# Power.net
KiCad netlist of a schematic drawn in Altium Designer
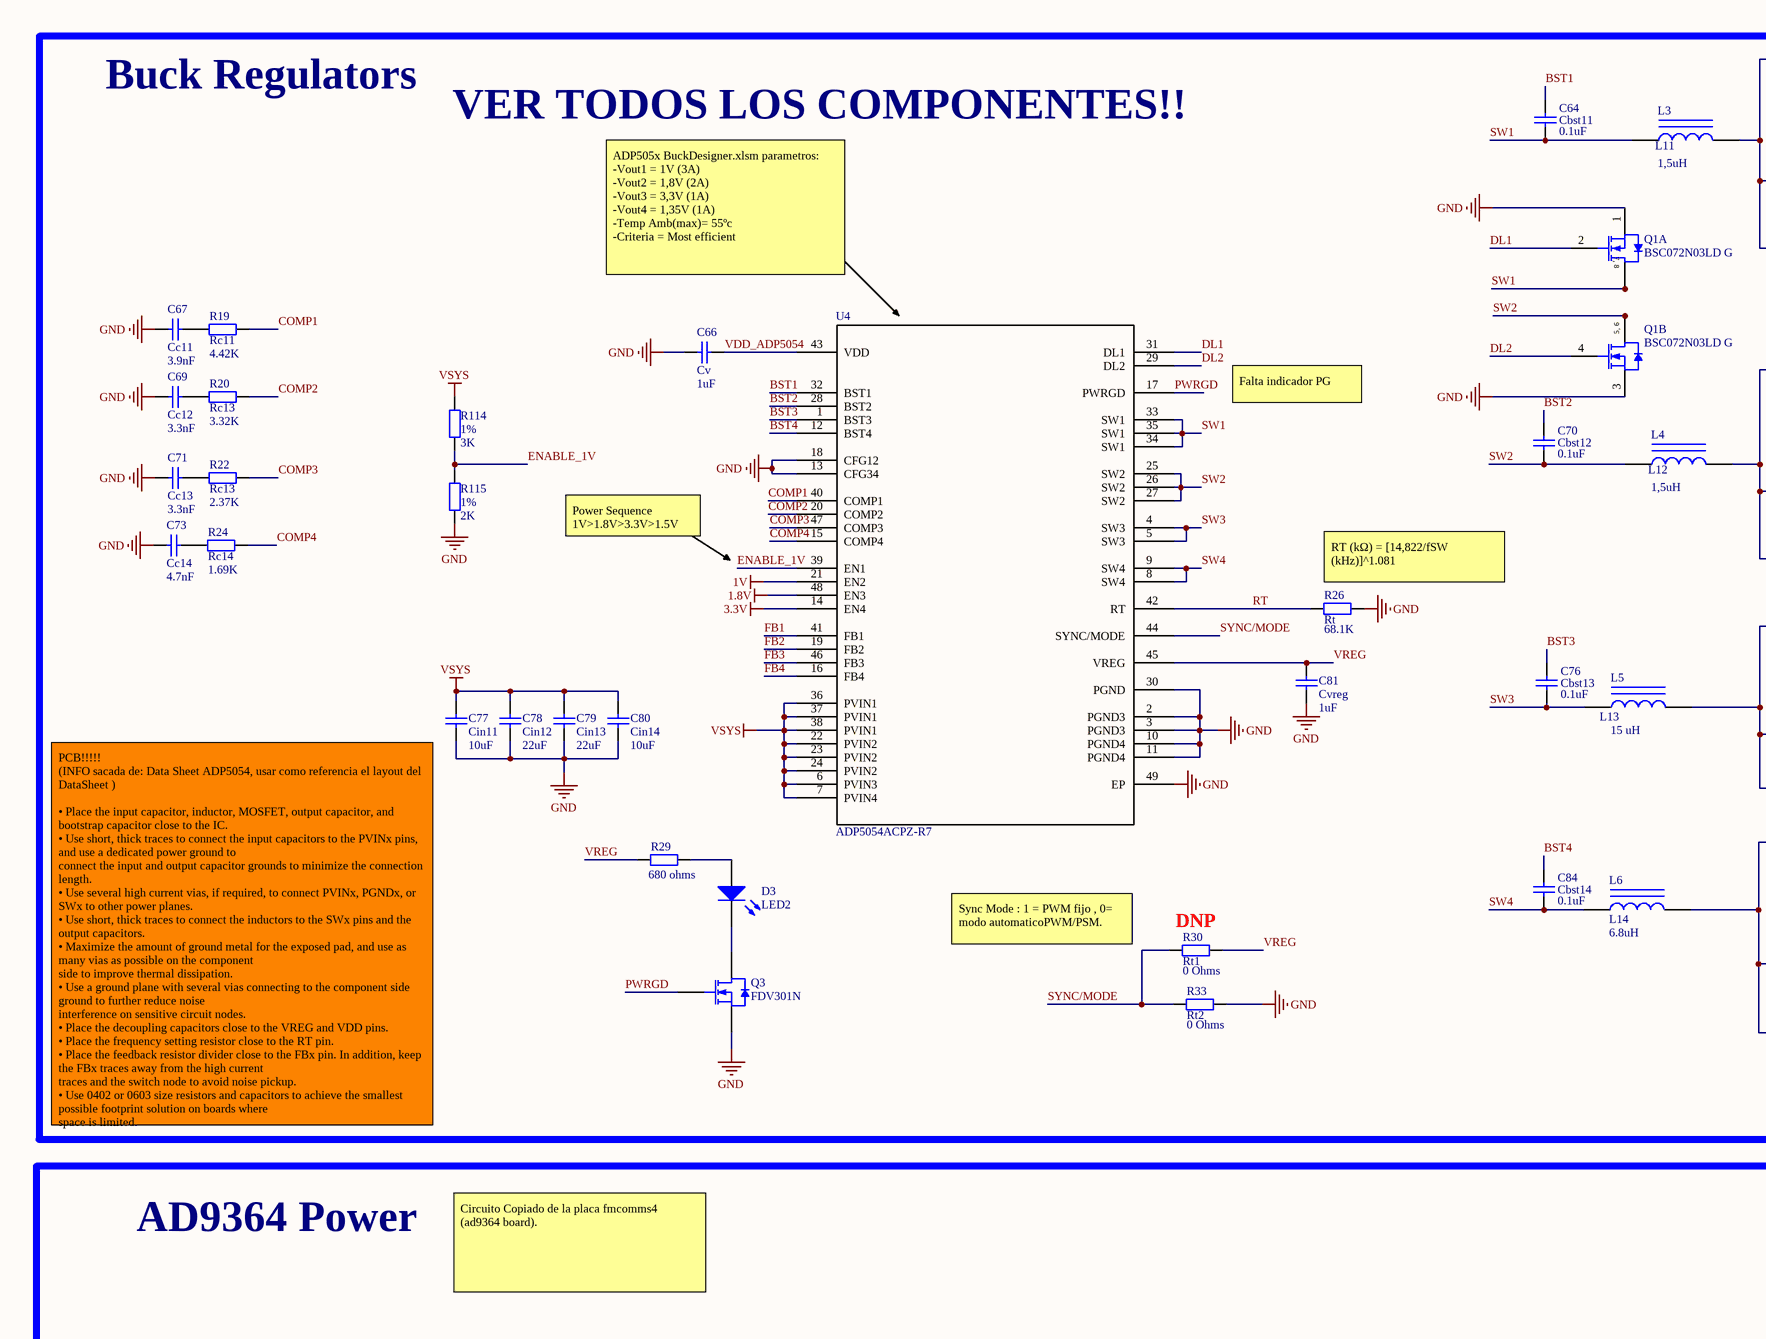
[diagram p0: Power.SchDoc, top left]
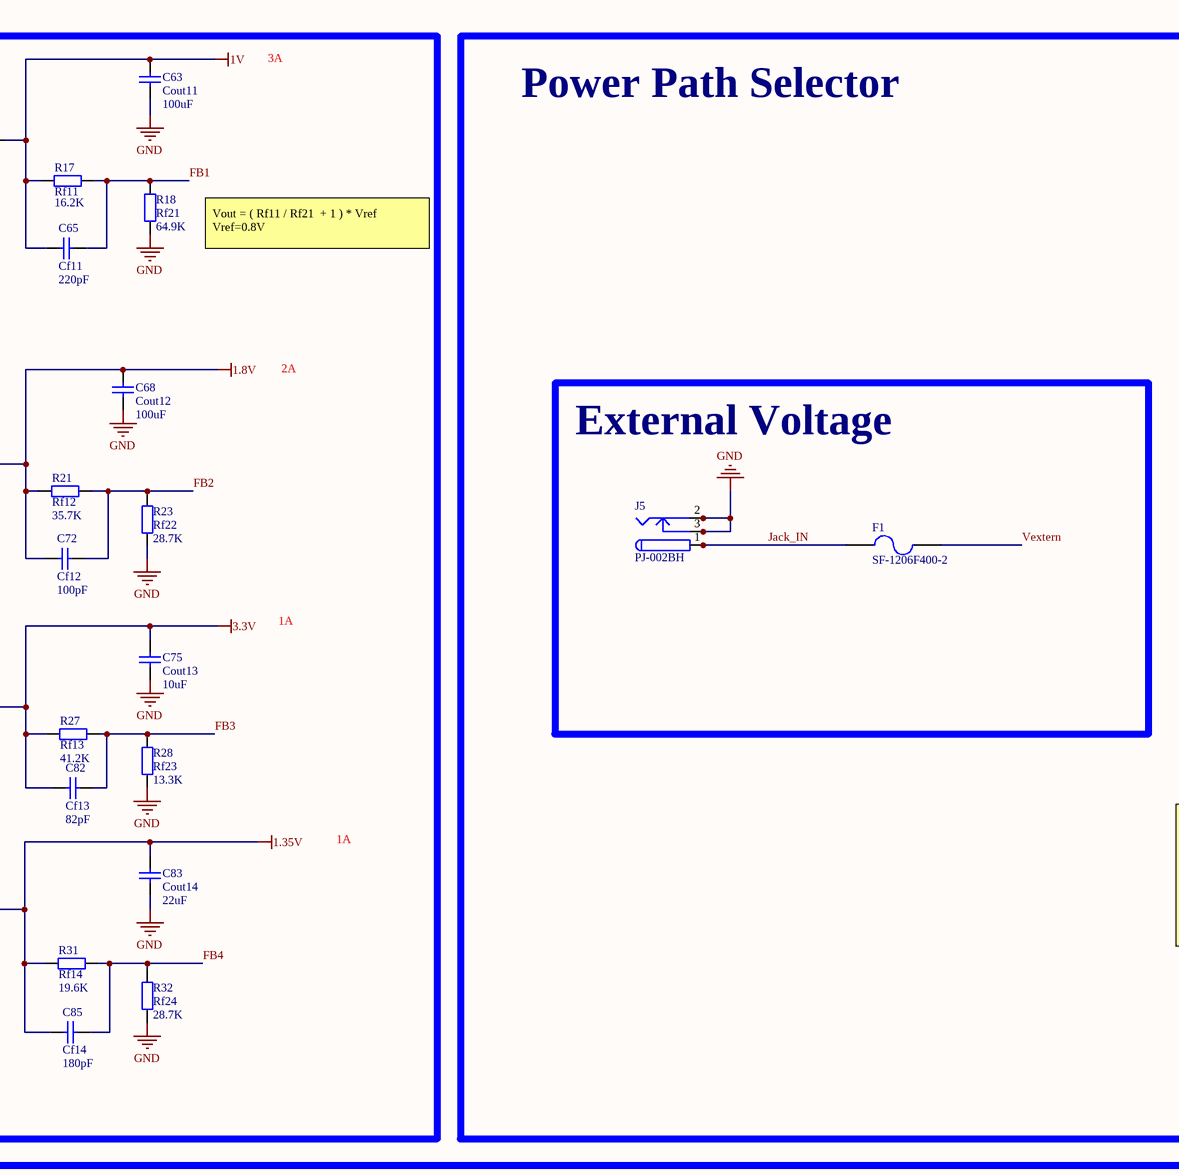
[diagram p1: Power.SchDoc, top middle]
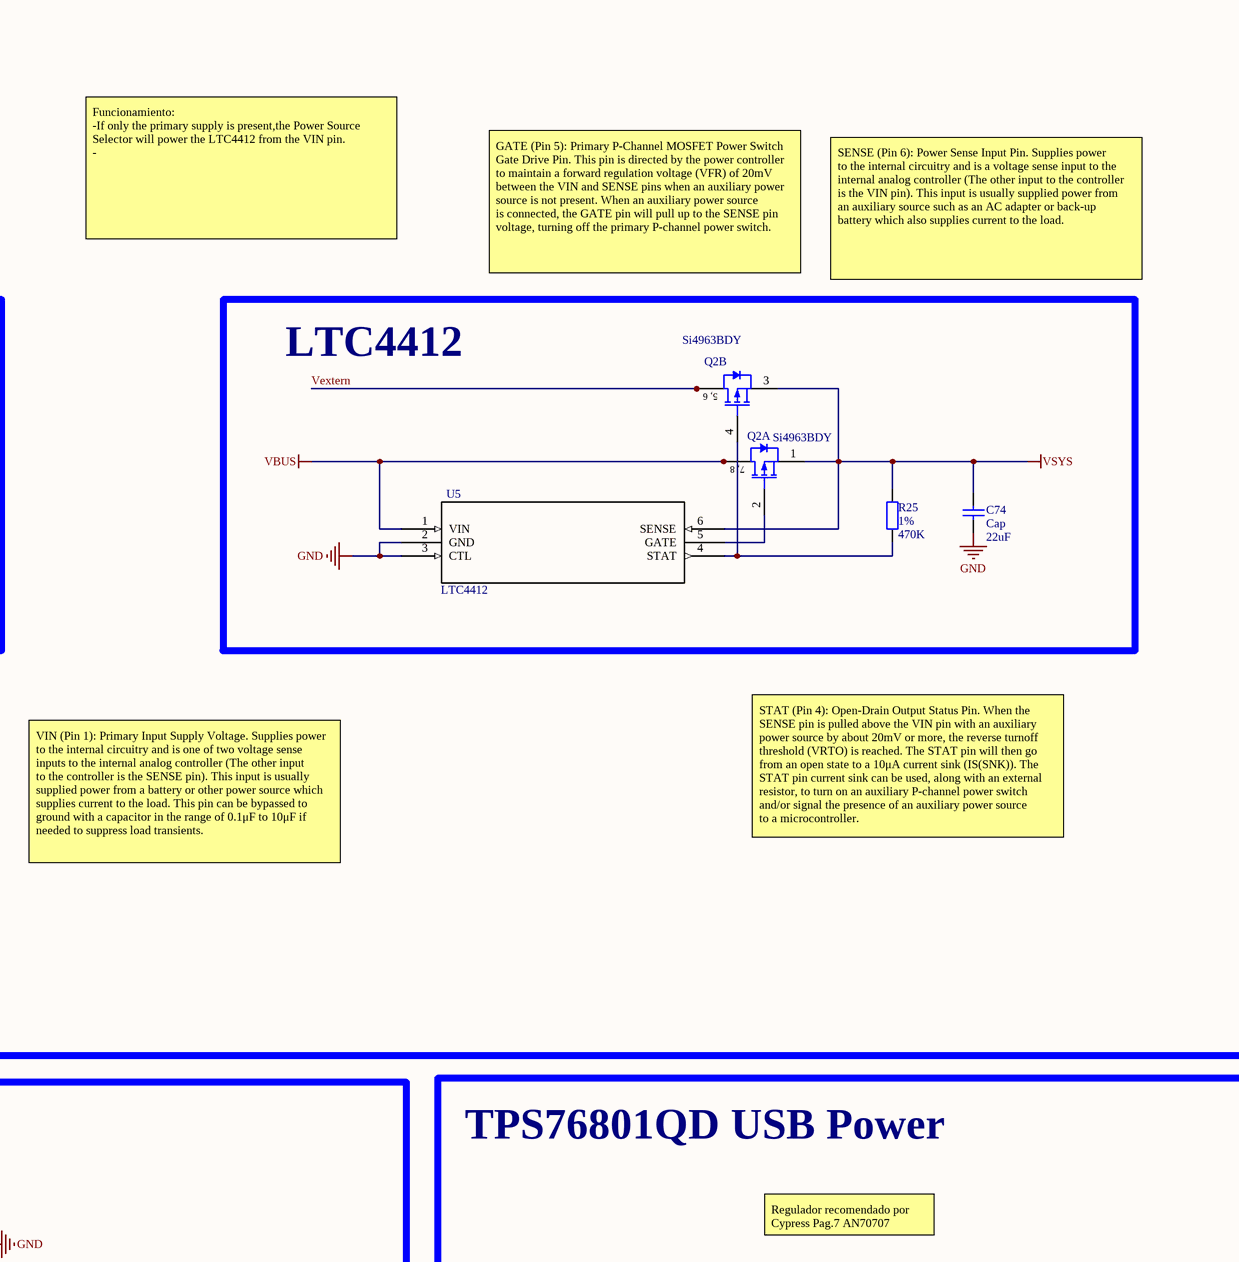
[diagram p2: Power.SchDoc, top right]
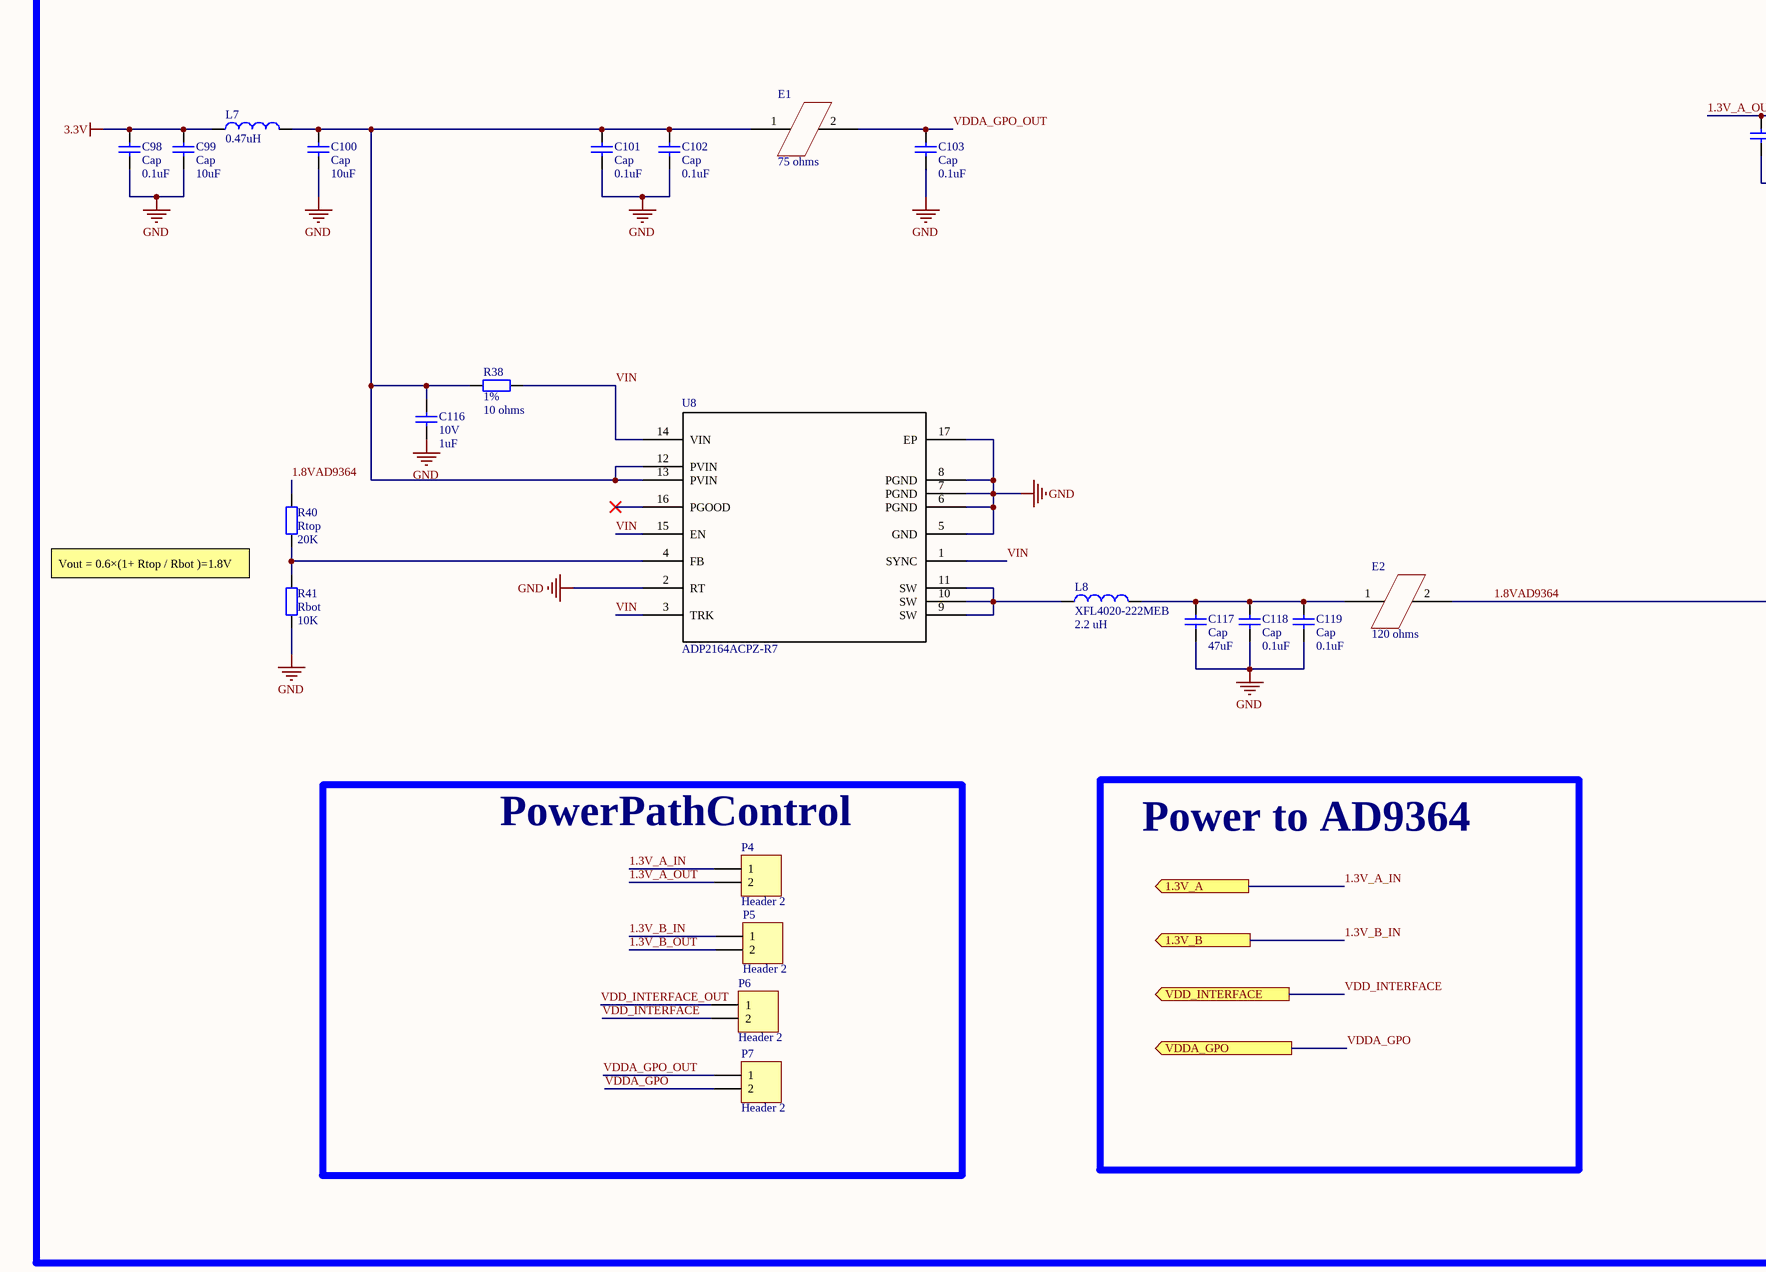
[diagram p3: Power.SchDoc, bottom left]
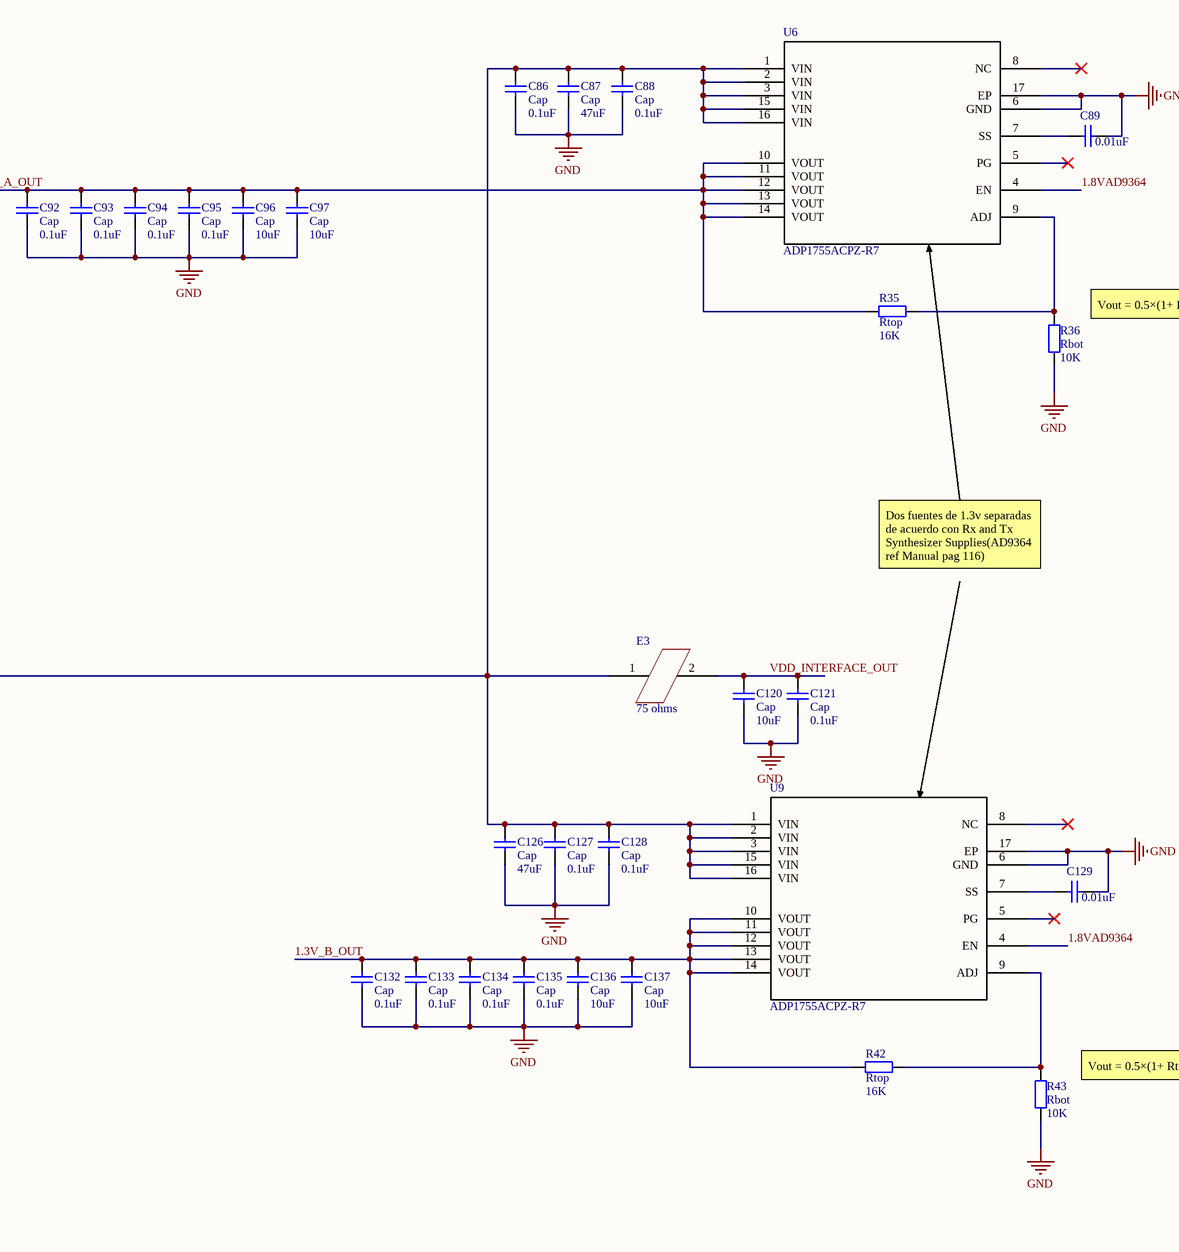
[diagram p4: Power.SchDoc, bottom middle]
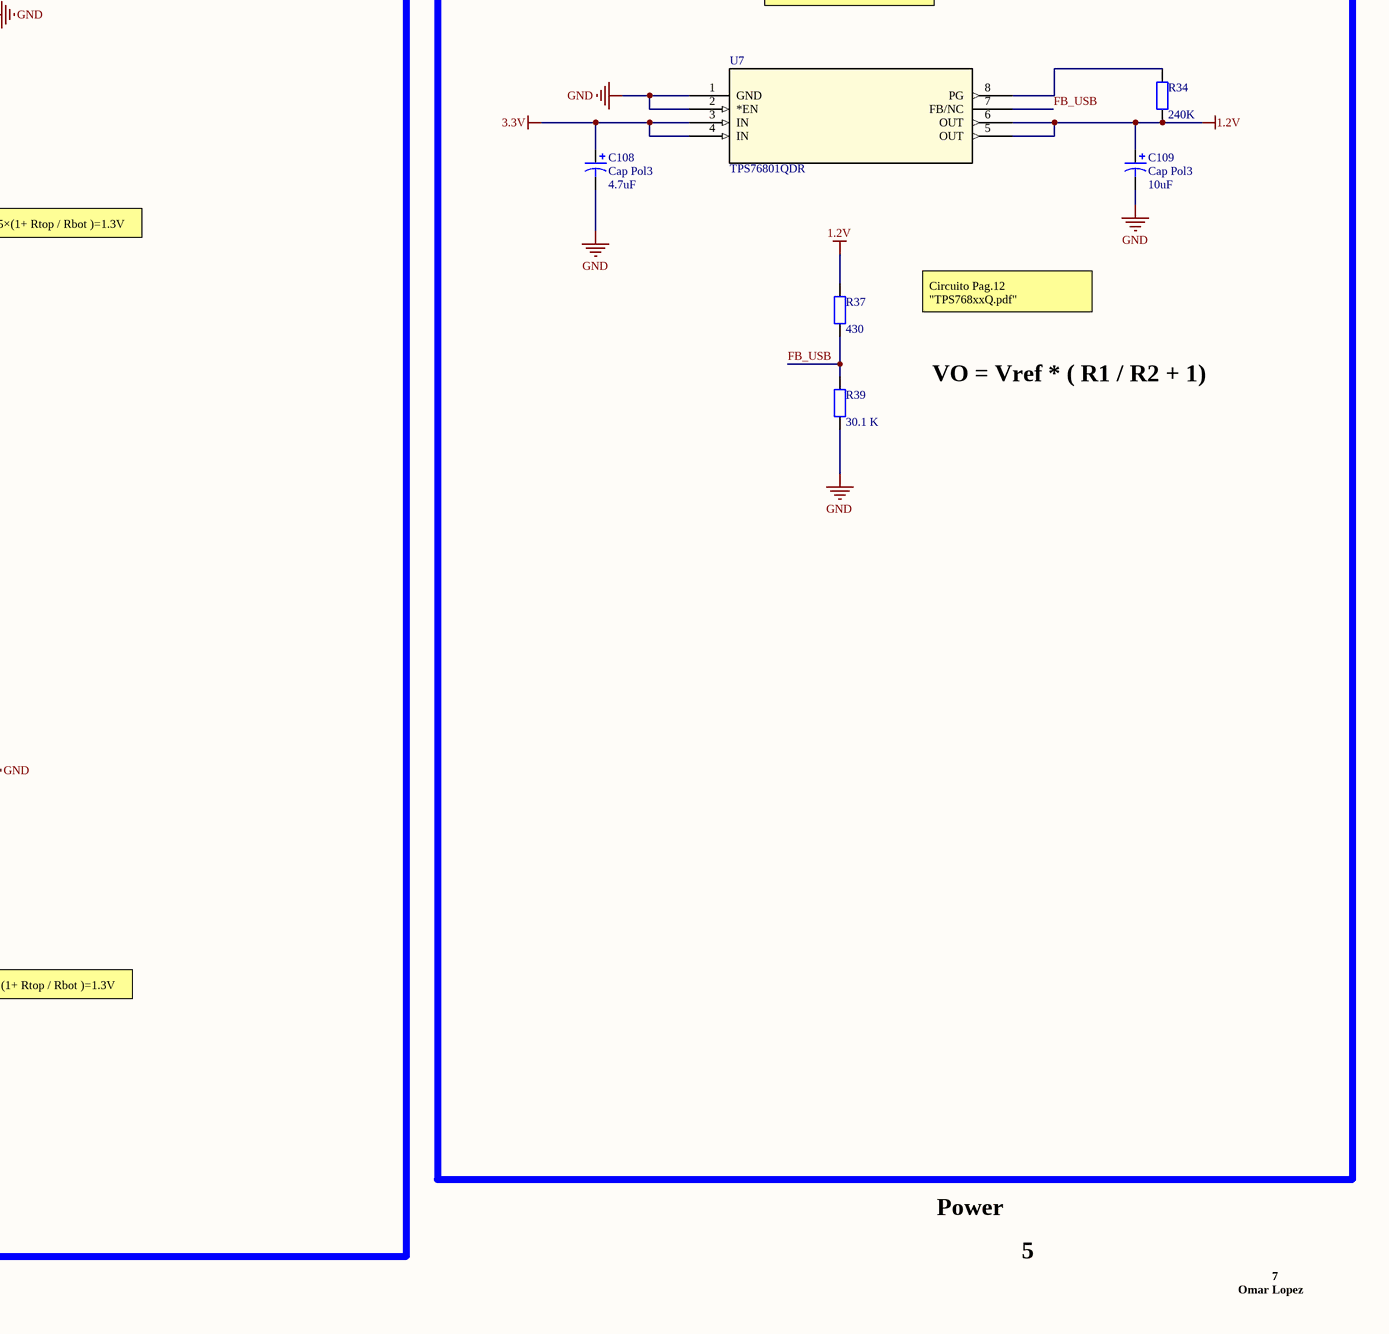
[diagram p5: Power.SchDoc, bottom right]

(export (version "E")
  (design (tool "Eeschema 10.0.6"))
  (components
    (comp (ref "C63")
      (value "Cout11")
      (footprint "MurataCapacitor:GRM1206MurataCap")
      (description "Capacitor")
      (fields
        (field (name "ALTIUM_VALUE") "100uF")
        (field (name "MANUFACTURER") "TDK")
        (field (name "TOLERANCE") "20%")
      )
      (libsource (lib "Miscellaneous Devices") (part "Cap"))
    )
    (comp (ref "C64")
      (value "Cbst11")
      (footprint "GRM0402MurataCap")
      (description "Capacitor")
      (fields
        (field (name "MANUFACTURER") "Murata")
        (field (name "PARTNUMBER") "GRM152D70G104ME15D")
        (field (name "ALTIUM_VALUE") "0.1uF")
      )
      (libsource (lib "Miscellaneous Devices") (part "Cap"))
    )
    (comp (ref "C65")
      (value "Cf11")
      (footprint "MurataCapacitor:GRM0402MurataCap")
      (description "Capacitor")
      (fields
        (field (name "ALTIUM_VALUE") "220pF")
        (field (name "MANUFACTURER") "Murata")
        (field (name "TOLERANCE") "5%")
      )
      (libsource (lib "Miscellaneous Devices") (part "Cap"))
    )
    (comp (ref "C66")
      (value "Cv")
      (footprint "MurataCapacitor:GRM0402MurataCap")
      (description "Capacitor")
      (fields
        (field (name "ALTIUM_VALUE") "1uF")
        (field (name "MANUFACTURER") "Murata")
        (field (name "TOLERANCE") "10%")
      )
      (libsource (lib "Miscellaneous Devices") (part "Cap"))
    )
    (comp (ref "C67")
      (value "Cc11")
      (footprint "MurataCapacitor:GRM0402MurataCap")
      (description "Capacitor")
      (fields
        (field (name "ALTIUM_VALUE") "3.9nF")
        (field (name "MANUFACTURER") "Murata")
        (field (name "TOLERANCE") "10%")
      )
      (libsource (lib "Miscellaneous Devices") (part "Cap"))
    )
    (comp (ref "C68")
      (value "Cout12")
      (footprint "MurataCapacitor:GRM1206MurataCap")
      (description "Capacitor")
      (fields
        (field (name "ALTIUM_VALUE") "100uF")
        (field (name "MANUFACTURER") "TDK")
        (field (name "TOLERANCE") "20%")
      )
      (libsource (lib "Miscellaneous Devices") (part "Cap"))
    )
    (comp (ref "C69")
      (value "Cc12")
      (footprint "MurataCapacitor:GRM0402MurataCap")
      (description "Capacitor")
      (fields
        (field (name "ALTIUM_VALUE") "3.3nF")
        (field (name "MANUFACTURER") "Murata")
        (field (name "TOLERANCE") "10%")
      )
      (libsource (lib "Miscellaneous Devices") (part "Cap"))
    )
    (comp (ref "C70")
      (value "Cbst12")
      (footprint "GRM0402MurataCap")
      (description "Capacitor")
      (fields
        (field (name "MANUFACTURER") "Murata")
        (field (name "PARTNUMBER") "GRM152D70G104ME15D")
        (field (name "ALTIUM_VALUE") "0.1uF")
      )
      (libsource (lib "Miscellaneous Devices") (part "Cap"))
    )
    (comp (ref "C71")
      (value "Cc13")
      (footprint "MurataCapacitor:GRM0402MurataCap")
      (description "Capacitor")
      (fields
        (field (name "ALTIUM_VALUE") "3.3nF")
        (field (name "MANUFACTURER") "Murata")
        (field (name "TOLERANCE") "10%")
      )
      (libsource (lib "Miscellaneous Devices") (part "Cap"))
    )
    (comp (ref "C72")
      (value "Cf12")
      (footprint "MurataCapacitor:GRM0402MurataCap")
      (description "Capacitor")
      (fields
        (field (name "ALTIUM_VALUE") "100pF")
        (field (name "MANUFACTURER") "Murata")
        (field (name "TOLERANCE") "2%")
      )
      (libsource (lib "Miscellaneous Devices") (part "Cap"))
    )
    (comp (ref "C73")
      (value "Cc14")
      (footprint "MurataCapacitor:GRM0402MurataCap")
      (description "Capacitor")
      (fields
        (field (name "ALTIUM_VALUE") "4.7nF")
        (field (name "MANUFACTURER") "Murata")
        (field (name "TOLERANCE") "10%")
      )
      (libsource (lib "Miscellaneous Devices") (part "Cap"))
    )
    (comp (ref "C74")
      (value "Cap")
      (footprint "MurataCapacitor:GRM1210MurataCap")
      (description "Capacitor")
      (fields
        (field (name "ALTIUM_VALUE") "22uF")
        (field (name "MANUFACTURER") "Taiyo Yuden")
        (field (name "TOLERANCE") "20%")
      )
      (libsource (lib "Miscellaneous Devices") (part "Cap"))
    )
    (comp (ref "C75")
      (value "Cout13")
      (footprint "MurataCapacitor:GRM1206MurataCap")
      (description "Capacitor")
      (fields
        (field (name "ALTIUM_VALUE") "10uF")
        (field (name "MANUFACTURER") "Taiyo Yuden")
        (field (name "TOLERANCE") "20%")
      )
      (libsource (lib "Miscellaneous Devices") (part "Cap"))
    )
    (comp (ref "C76")
      (value "Cbst13")
      (footprint "GRM0402MurataCap")
      (description "Capacitor")
      (fields
        (field (name "MANUFACTURER") "Murata")
        (field (name "PARTNUMBER") "GRM152D70G104ME15D")
        (field (name "ALTIUM_VALUE") "0.1uF")
      )
      (libsource (lib "Miscellaneous Devices") (part "Cap"))
    )
    (comp (ref "C77")
      (value "Cin11")
      (footprint "MurataCapacitor:GRM1210MurataCap")
      (description "Capacitor")
      (fields
        (field (name "ALTIUM_VALUE") "10uF")
        (field (name "MANUFACTURER") "Murata")
        (field (name "TOLERANCE") "10%")
      )
      (libsource (lib "Miscellaneous Devices") (part "Cap"))
    )
    (comp (ref "C78")
      (value "Cin12")
      (footprint "MurataCapacitor:GRM1210MurataCap")
      (description "Capacitor")
      (fields
        (field (name "ALTIUM_VALUE") "22uF")
        (field (name "MANUFACTURER") "Taiyo Yuden")
        (field (name "TOLERANCE") "20%")
      )
      (libsource (lib "Miscellaneous Devices") (part "Cap"))
    )
    (comp (ref "C79")
      (value "Cin13")
      (footprint "MurataCapacitor:GRM1210MurataCap")
      (description "Capacitor")
      (fields
        (field (name "ALTIUM_VALUE") "22uF")
        (field (name "MANUFACTURER") "Taiyo Yuden")
        (field (name "TOLERANCE") "20%")
      )
      (libsource (lib "Miscellaneous Devices") (part "Cap"))
    )
    (comp (ref "C80")
      (value "Cin14")
      (footprint "MurataCapacitor:GRM1210MurataCap")
      (description "Capacitor")
      (fields
        (field (name "ALTIUM_VALUE") "10uF")
        (field (name "MANUFACTURER") "Murata")
        (field (name "TOLERANCE") "10%")
      )
      (libsource (lib "Miscellaneous Devices") (part "Cap"))
    )
    (comp (ref "C81")
      (value "Cvreg")
      (footprint "MurataCapacitor:GRM0402MurataCap")
      (description "Capacitor")
      (fields
        (field (name "ALTIUM_VALUE") "1uF")
        (field (name "MANUFACTURER") "Murata")
        (field (name "TOLERANCE") "10%")
      )
      (libsource (lib "Miscellaneous Devices") (part "Cap"))
    )
    (comp (ref "C82")
      (value "Cf13")
      (footprint "MurataCapacitor:GRM0402MurataCap")
      (description "Capacitor")
      (fields
        (field (name "ALTIUM_VALUE") "82pF")
        (field (name "MANUFACTURER") "Murata")
        (field (name "TOLERANCE") "10%")
      )
      (libsource (lib "Miscellaneous Devices") (part "Cap"))
    )
    (comp (ref "C83")
      (value "Cout14")
      (footprint "MurataCapacitor:GRM1206MurataCap")
      (description "Capacitor")
      (fields
        (field (name "ALTIUM_VALUE") "22uF")
        (field (name "MANUFACTURER") "Taiyo Yuden")
        (field (name "TOLERANCE") "20%")
      )
      (libsource (lib "Miscellaneous Devices") (part "Cap"))
    )
    (comp (ref "C84")
      (value "Cbst14")
      (footprint "GRM0402MurataCap")
      (description "Capacitor")
      (fields
        (field (name "MANUFACTURER") "Murata")
        (field (name "PARTNUMBER") "GRM152D70G104ME15D")
        (field (name "ALTIUM_VALUE") "0.1uF")
      )
      (libsource (lib "Miscellaneous Devices") (part "Cap"))
    )
    (comp (ref "C85")
      (value "Cf14")
      (footprint "MurataCapacitor:GRM0402MurataCap")
      (description "Capacitor")
      (fields
        (field (name "ALTIUM_VALUE") "180pF")
        (field (name "MANUFACTURER") "Murata")
        (field (name "TOLERANCE") "5%")
      )
      (libsource (lib "Miscellaneous Devices") (part "Cap"))
    )
    (comp (ref "C86")
      (value "Cap")
      (footprint "MurataCapacitor:GRM0402MurataCap")
      (description "Capacitor")
      (fields
        (field (name "ALTIUM_VALUE") "0.1uF")
        (field (name "MANUFACTURER") "Murata")
        (field (name "TOLERANCE") "10%")
      )
      (libsource (lib "Miscellaneous Devices") (part "Cap"))
    )
    (comp (ref "C87")
      (value "Cap")
      (footprint "MurataCapacitor:GRM0805MurataCap")
      (description "Capacitor")
      (fields
        (field (name "ALTIUM_VALUE") "47uF")
        (field (name "MANUFACTURER") "Murata")
        (field (name "TOLERANCE") "20%")
      )
      (libsource (lib "Miscellaneous Devices") (part "Cap"))
    )
    (comp (ref "C88")
      (value "Cap")
      (footprint "MurataCapacitor:GRM0402MurataCap")
      (description "Capacitor")
      (fields
        (field (name "ALTIUM_VALUE") "0.1uF")
        (field (name "MANUFACTURER") "Murata")
        (field (name "TOLERANCE") "10%")
      )
      (libsource (lib "Miscellaneous Devices") (part "Cap"))
    )
    (comp (ref "C89")
      (value "0.01uF")
      (footprint "MurataCapacitor:GRM0402MurataCap")
      (description "Capacitor")
      (fields (field (name "MANUFACTURER") "Murata") (field (name "TOLERANCE") "10%"))
      (libsource (lib "Miscellaneous Devices") (part "Cap"))
    )
    (comp (ref "C92")
      (value "Cap")
      (footprint "MurataCapacitor:GRM0402MurataCap")
      (description "Capacitor")
      (fields
        (field (name "ALTIUM_VALUE") "0.1uF")
        (field (name "MANUFACTURER") "Murata")
        (field (name "TOLERANCE") "10%")
      )
      (libsource (lib "Miscellaneous Devices") (part "Cap"))
    )
    (comp (ref "C93")
      (value "Cap")
      (footprint "MurataCapacitor:GRM0402MurataCap")
      (description "Capacitor")
      (fields
        (field (name "ALTIUM_VALUE") "0.1uF")
        (field (name "MANUFACTURER") "Murata")
        (field (name "TOLERANCE") "10%")
      )
      (libsource (lib "Miscellaneous Devices") (part "Cap"))
    )
    (comp (ref "C94")
      (value "Cap")
      (footprint "MurataCapacitor:GRM0402MurataCap")
      (description "Capacitor")
      (fields
        (field (name "ALTIUM_VALUE") "0.1uF")
        (field (name "MANUFACTURER") "Murata")
        (field (name "TOLERANCE") "10%")
      )
      (libsource (lib "Miscellaneous Devices") (part "Cap"))
    )
    (comp (ref "C95")
      (value "Cap")
      (footprint "MurataCapacitor:GRM0402MurataCap")
      (description "Capacitor")
      (fields
        (field (name "ALTIUM_VALUE") "0.1uF")
        (field (name "MANUFACTURER") "Murata")
        (field (name "TOLERANCE") "10%")
      )
      (libsource (lib "Miscellaneous Devices") (part "Cap"))
    )
    (comp (ref "C96")
      (value "Cap")
      (footprint "MurataCapacitor:GRM0603MurataCap")
      (description "Capacitor")
      (fields
        (field (name "ALTIUM_VALUE") "10uF")
        (field (name "MANUFACTURER") "Murata")
        (field (name "TOLERANCE") "20%")
      )
      (libsource (lib "Miscellaneous Devices") (part "Cap"))
    )
    (comp (ref "C97")
      (value "Cap")
      (footprint "MurataCapacitor:GRM0603MurataCap")
      (description "Capacitor")
      (fields
        (field (name "ALTIUM_VALUE") "10uF")
        (field (name "MANUFACTURER") "Murata")
        (field (name "TOLERANCE") "20%")
      )
      (libsource (lib "Miscellaneous Devices") (part "Cap"))
    )
    (comp (ref "C98")
      (value "Cap")
      (footprint "MurataCapacitor:GRM0402MurataCap")
      (description "Capacitor")
      (fields
        (field (name "ALTIUM_VALUE") "0.1uF")
        (field (name "MANUFACTURER") "Murata")
        (field (name "TOLERANCE") "10%")
      )
      (libsource (lib "Miscellaneous Devices") (part "Cap"))
    )
    (comp (ref "C99")
      (value "Cap")
      (footprint "MurataCapacitor:GRM0603MurataCap")
      (description "Capacitor")
      (fields
        (field (name "ALTIUM_VALUE") "10uF")
        (field (name "MANUFACTURER") "Murata")
        (field (name "TOLERANCE") "20%")
      )
      (libsource (lib "Miscellaneous Devices") (part "Cap"))
    )
    (comp (ref "C100")
      (value "Cap")
      (footprint "MurataCapacitor:GRM0603MurataCap")
      (description "Capacitor")
      (fields
        (field (name "ALTIUM_VALUE") "10uF")
        (field (name "MANUFACTURER") "Murata")
        (field (name "TOLERANCE") "20%")
      )
      (libsource (lib "Miscellaneous Devices") (part "Cap"))
    )
    (comp (ref "C101")
      (value "Cap")
      (footprint "MurataCapacitor:GRM0402MurataCap")
      (description "Capacitor")
      (fields
        (field (name "ALTIUM_VALUE") "0.1uF")
        (field (name "MANUFACTURER") "Murata")
        (field (name "TOLERANCE") "10%")
      )
      (libsource (lib "Miscellaneous Devices") (part "Cap"))
    )
    (comp (ref "C102")
      (value "Cap")
      (footprint "MurataCapacitor:GRM0402MurataCap")
      (description "Capacitor")
      (fields
        (field (name "ALTIUM_VALUE") "0.1uF")
        (field (name "MANUFACTURER") "Murata")
        (field (name "TOLERANCE") "10%")
      )
      (libsource (lib "Miscellaneous Devices") (part "Cap"))
    )
    (comp (ref "C103")
      (value "Cap")
      (footprint "MurataCapacitor:GRM0402MurataCap")
      (description "Capacitor")
      (fields
        (field (name "ALTIUM_VALUE") "0.1uF")
        (field (name "MANUFACTURER") "Murata")
        (field (name "TOLERANCE") "10%")
      )
      (libsource (lib "Miscellaneous Devices") (part "Cap"))
    )
    (comp (ref "C108")
      (value "Cap Pol3")
      (footprint "CapTal:CapTalCaseM")
      (description "Polarized Capacitor (Surface Mount)")
      (fields
        (field (name "ALTIUM_VALUE") "4.7uF")
        (field (name "TOLERANCE") "20%")
        (field (name "PARTNUMBER") "298D475X0016M2T")
      )
      (libsource (lib "Miscellaneous Devices") (part "Cap Pol3"))
    )
    (comp (ref "C109")
      (value "Cap Pol3")
      (footprint "TAJ_Cap:TAJ_DorE2917")
      (description "Polarized Capacitor (Surface Mount)")
      (fields
        (field (name "ALTIUM_VALUE") "10uF")
        (field (name "TOLERANCE") "30%")
        (field (name "PARTNUMBER") "TAJD106K035RNJ")
      )
      (libsource (lib "Miscellaneous Devices") (part "Cap Pol3"))
    )
    (comp (ref "C116")
      (value "10V")
      (footprint "MurataCapacitor:GRM0402MurataCap")
      (description "Capacitor")
      (fields
        (field (name "ALTIUM_VALUE") "1uF")
        (field (name "MANUFACTURER") "Murata")
        (field (name "TOLERANCE") "10%")
      )
      (libsource (lib "Miscellaneous Devices") (part "Cap"))
    )
    (comp (ref "C117")
      (value "Cap")
      (footprint "MurataCapacitor:GRM0805MurataCap")
      (description "Capacitor")
      (fields
        (field (name "ALTIUM_VALUE") "47uF")
        (field (name "MANUFACTURER") "Murata")
        (field (name "TOLERANCE") "20%")
      )
      (libsource (lib "Miscellaneous Devices") (part "Cap"))
    )
    (comp (ref "C118")
      (value "Cap")
      (footprint "MurataCapacitor:GRM0402MurataCap")
      (description "Capacitor")
      (fields
        (field (name "ALTIUM_VALUE") "0.1uF")
        (field (name "MANUFACTURER") "Murata")
        (field (name "TOLERANCE") "10%")
      )
      (libsource (lib "Miscellaneous Devices") (part "Cap"))
    )
    (comp (ref "C119")
      (value "Cap")
      (footprint "MurataCapacitor:GRM0402MurataCap")
      (description "Capacitor")
      (fields
        (field (name "ALTIUM_VALUE") "0.1uF")
        (field (name "MANUFACTURER") "Murata")
        (field (name "TOLERANCE") "10%")
      )
      (libsource (lib "Miscellaneous Devices") (part "Cap"))
    )
    (comp (ref "C120")
      (value "Cap")
      (footprint "MurataCapacitor:GRM0603MurataCap")
      (description "Capacitor")
      (fields
        (field (name "ALTIUM_VALUE") "10uF")
        (field (name "MANUFACTURER") "Murata")
        (field (name "TOLERANCE") "20%")
      )
      (libsource (lib "Miscellaneous Devices") (part "Cap"))
    )
    (comp (ref "C121")
      (value "Cap")
      (footprint "MurataCapacitor:GRM0402MurataCap")
      (description "Capacitor")
      (fields
        (field (name "ALTIUM_VALUE") "0.1uF")
        (field (name "MANUFACTURER") "Murata")
        (field (name "TOLERANCE") "10%")
      )
      (libsource (lib "Miscellaneous Devices") (part "Cap"))
    )
    (comp (ref "C126")
      (value "Cap")
      (footprint "MurataCapacitor:GRM0805MurataCap")
      (description "Capacitor")
      (fields
        (field (name "ALTIUM_VALUE") "47uF")
        (field (name "MANUFACTURER") "Murata")
        (field (name "TOLERANCE") "20%")
      )
      (libsource (lib "Miscellaneous Devices") (part "Cap"))
    )
    (comp (ref "C127")
      (value "Cap")
      (footprint "MurataCapacitor:GRM0402MurataCap")
      (description "Capacitor")
      (fields
        (field (name "ALTIUM_VALUE") "0.1uF")
        (field (name "MANUFACTURER") "Murata")
        (field (name "TOLERANCE") "10%")
      )
      (libsource (lib "Miscellaneous Devices") (part "Cap"))
    )
    (comp (ref "C128")
      (value "Cap")
      (footprint "MurataCapacitor:GRM0402MurataCap")
      (description "Capacitor")
      (fields
        (field (name "ALTIUM_VALUE") "0.1uF")
        (field (name "MANUFACTURER") "Murata")
        (field (name "TOLERANCE") "10%")
      )
      (libsource (lib "Miscellaneous Devices") (part "Cap"))
    )
    (comp (ref "C129")
      (value "0.01uF")
      (footprint "MurataCapacitor:GRM0402MurataCap")
      (description "Capacitor")
      (fields (field (name "MANUFACTURER") "Murata") (field (name "TOLERANCE") "10%"))
      (libsource (lib "Miscellaneous Devices") (part "Cap"))
    )
    (comp (ref "C132")
      (value "Cap")
      (footprint "MurataCapacitor:GRM0402MurataCap")
      (description "Capacitor")
      (fields
        (field (name "ALTIUM_VALUE") "0.1uF")
        (field (name "MANUFACTURER") "Murata")
        (field (name "TOLERANCE") "10%")
      )
      (libsource (lib "Miscellaneous Devices") (part "Cap"))
    )
    (comp (ref "C133")
      (value "Cap")
      (footprint "MurataCapacitor:GRM0402MurataCap")
      (description "Capacitor")
      (fields
        (field (name "ALTIUM_VALUE") "0.1uF")
        (field (name "MANUFACTURER") "Murata")
        (field (name "TOLERANCE") "10%")
      )
      (libsource (lib "Miscellaneous Devices") (part "Cap"))
    )
    (comp (ref "C134")
      (value "Cap")
      (footprint "MurataCapacitor:GRM0402MurataCap")
      (description "Capacitor")
      (fields
        (field (name "ALTIUM_VALUE") "0.1uF")
        (field (name "MANUFACTURER") "Murata")
        (field (name "TOLERANCE") "10%")
      )
      (libsource (lib "Miscellaneous Devices") (part "Cap"))
    )
    (comp (ref "C135")
      (value "Cap")
      (footprint "MurataCapacitor:GRM0402MurataCap")
      (description "Capacitor")
      (fields
        (field (name "ALTIUM_VALUE") "0.1uF")
        (field (name "MANUFACTURER") "Murata")
        (field (name "TOLERANCE") "10%")
      )
      (libsource (lib "Miscellaneous Devices") (part "Cap"))
    )
    (comp (ref "C136")
      (value "Cap")
      (footprint "MurataCapacitor:GRM0603MurataCap")
      (description "Capacitor")
      (fields
        (field (name "ALTIUM_VALUE") "10uF")
        (field (name "MANUFACTURER") "Murata")
        (field (name "TOLERANCE") "20%")
      )
      (libsource (lib "Miscellaneous Devices") (part "Cap"))
    )
    (comp (ref "C137")
      (value "Cap")
      (footprint "MurataCapacitor:GRM0603MurataCap")
      (description "Capacitor")
      (fields
        (field (name "ALTIUM_VALUE") "10uF")
        (field (name "MANUFACTURER") "Murata")
        (field (name "TOLERANCE") "20%")
      )
      (libsource (lib "Miscellaneous Devices") (part "Cap"))
    )
    (comp (ref "D3")
      (value "LED2")
      (footprint "LiteOnLed:LTSTC191")
      (description "Typical RED, GREEN, YELLOW, AMBER GaAs LED")
      (fields (field (name "MANUFACTURER") "Panasonic") (field (name "PARTNUMBER") "LTST-C193TGKT-5A"))
      (libsource (lib "Miscellaneous Devices") (part "LED2"))
    )
    (comp (ref "E1")
      (value "75 ohms")
      (footprint "BLM15BA750SN1D:BLM15BA750SN1D")
      (description "Ferrite bead")
      (fields (field (name "MANUFACTURER") "Murata") (field (name "PARTNUMBER") "BLM15BA750SN1D"))
      (libsource (lib "FerriteBead") (part "Ferrite Bead"))
    )
    (comp (ref "E2")
      (value "120 ohms")
      (footprint "BLM15BA750SN1D:BLM15BA750SN1D")
      (description "Ferrite bead")
      (fields (field (name "MANUFACTURER") "Murata") (field (name "PARTNUMBER") "BLM15EG121SN1D"))
      (libsource (lib "FerriteBead") (part "Ferrite Bead"))
    )
    (comp (ref "E3")
      (value "75 ohms")
      (footprint "BLM15BA750SN1D:BLM15BA750SN1D")
      (description "Ferrite bead")
      (fields (field (name "MANUFACTURER") "Murata") (field (name "PARTNUMBER") "BLM15BA750SN1D"))
      (libsource (lib "FerriteBead") (part "Ferrite Bead"))
    )
    (comp (ref "F1")
      (value "SF-1206F400-2")
      (footprint "FUSE:SF-1206F400-2")
      (description "Fuse")
      (fields (field (name "MANUFACTURER") "Bourns"))
      (libsource (lib "Miscellaneous Devices") (part "Fuse 2"))
    )
    (comp (ref "J5")
      (value "PJ-002BH")
      (footprint "DCPowerJack:PJ-002BH")
      (description "Low Voltage Power Supply Connector")
      (fields (field (name "MANUFACTURER") "CUI"))
      (libsource (lib "Miscellaneous Connectors") (part "PWR2.5"))
    )
    (comp (ref "L3")
      (value "L11")
      (footprint "CoilcraftPCB:XAL4040-152")
      (description "Magnetic-Core Inductor")
      (fields
        (field (name "ALTIUM_VALUE") "1,5uH")
        (field (name "MANUFACTURER") "Coilcraft")
        (field (name "TOLERANCE") "20%")
      )
      (libsource (lib "Miscellaneous Devices") (part "Inductor Iron"))
    )
    (comp (ref "L4")
      (value "L12")
      (footprint "CoilcraftPCB:XAL4040-152")
      (description "Magnetic-Core Inductor")
      (fields
        (field (name "ALTIUM_VALUE") "1,5uH")
        (field (name "MANUFACTURER") "Coilcraft")
        (field (name "TOLERANCE") "20%")
      )
      (libsource (lib "Miscellaneous Devices") (part "Inductor Iron"))
    )
    (comp (ref "L5")
      (value "L13")
      (footprint "CoilcraftPCB:XAL5050-153")
      (description "Magnetic-Core Inductor")
      (fields
        (field (name "ALTIUM_VALUE") "15 uH")
        (field (name "MANUFACTURER") "Coilcraft")
        (field (name "TOLERANCE") "20%")
      )
      (libsource (lib "Miscellaneous Devices") (part "Inductor Iron"))
    )
    (comp (ref "L6")
      (value "L14")
      (footprint "CoilcraftPCB:XAL8080-682")
      (description "Magnetic-Core Inductor")
      (fields
        (field (name "ALTIUM_VALUE") "6.8uH")
        (field (name "MANUFACTURER") "Coilcraft")
        (field (name "TOLERANCE") "20%")
      )
      (libsource (lib "Miscellaneous Devices") (part "Inductor Iron"))
    )
    (comp (ref "L7")
      (value "0.47uH")
      (footprint "LQH32PNR47NN0L:LQH32PNR47NN0L")
      (description "Inductor")
      (fields (field (name "MANUFACTURER") "Murata") (field (name "PARTNUMBER") "LQH32PNR47NN0L"))
      (libsource (lib "Miscellaneous Devices") (part "Inductor"))
    )
    (comp (ref "L8")
      (value "XFL4020-222MEB")
      (footprint "CoilcraftPCB:XFL4020 SERIES")
      (description "Inductor")
      (fields
        (field (name "ALTIUM_VALUE") "2.2 uH")
        (field (name "MANUFACTURER") "Coilcraft")
        (field (name "TOLERANCE") "20%")
      )
      (libsource (lib "Miscellaneous Devices") (part "Inductor"))
    )
    (comp (ref "P4")
      (value "Header 2")
      (footprint "Header2x1")
      (description "Header, 2-Pin")
      (fields (field (name "MANUFACTURER") "TE Connectivity") (field (name "PARTNUMBER") "826629"))
      (libsource (lib "Miscellaneous Connectors") (part "Header 2"))
    )
    (comp (ref "P5")
      (value "Header 2")
      (footprint "Header2x1")
      (description "Header, 2-Pin")
      (fields (field (name "MANUFACTURER") "TE Connectivity") (field (name "PARTNUMBER") "826629"))
      (libsource (lib "Miscellaneous Connectors") (part "Header 2"))
    )
    (comp (ref "P6")
      (value "Header 2")
      (footprint "Header2x1")
      (description "Header, 2-Pin")
      (fields (field (name "MANUFACTURER") "TE Connectivity") (field (name "PARTNUMBER") "826629"))
      (libsource (lib "Miscellaneous Connectors") (part "Header 2"))
    )
    (comp (ref "P7")
      (value "Header 2")
      (footprint "Header2x1")
      (description "Header, 2-Pin")
      (fields (field (name "MANUFACTURER") "TE Connectivity") (field (name "PARTNUMBER") "826629"))
      (libsource (lib "Miscellaneous Connectors") (part "Header 2"))
    )
    (comp (ref "Q1")
      (value "BSC072N03LD G")
      (footprint "INF-PG-TDSON-8-4_V")
      (fields (field (name "MANUFACTURER") "Infineon"))
      (libsource (lib "Infineon_Power_MOSFET") (part "BSC072N03LD G"))
    )
    (comp (ref "Q2")
      (value "Si4963BDY")
      (footprint "SO-8_N")
      (description "Dual P-Channel 30V (D-S)  MOSFET")
      (libsource (lib "Vishay Siliconix Discrete MOSFET") (part "SI4925DY"))
    )
    (comp (ref "Q3")
      (value "FDV301N")
      (footprint "SOT-23B")
      (description "N-Channel 60V (D-S), 175'C  MOSFET")
      (fields (field (name "MANUFACTURER") "On Semiconductor"))
      (libsource (lib "Vishay Siliconix Discrete MOSFET") (part "SUP70N06-14"))
    )
    (comp (ref "R17")
      (value "Rf11")
      (footprint "Res0402ERJ:RC0402N")
      (description "Resistor")
      (fields
        (field (name "ALTIUM_VALUE") "16.2K")
        (field (name "MANUFACTURER") "Panasonic")
        (field (name "TOLERANCE") "1%")
      )
      (libsource (lib "") (part "Res2_3"))
    )
    (comp (ref "R18")
      (value "Rf21")
      (footprint "Res0402ERJ:RC0402N")
      (description "Resistor")
      (fields
        (field (name "ALTIUM_VALUE") "64.9K")
        (field (name "MANUFACTURER") "Panasonic")
        (field (name "TOLERANCE") "1%")
      )
      (libsource (lib "") (part "Res2_2"))
    )
    (comp (ref "R19")
      (value "Rc11")
      (footprint "Res0402ERJ:RC0402N")
      (description "Resistor")
      (fields
        (field (name "ALTIUM_VALUE") "4.42K")
        (field (name "MANUFACTURER") "Panasonic")
        (field (name "TOLERANCE") "1%")
      )
      (libsource (lib "Miscellaneous Devices") (part "Res2"))
    )
    (comp (ref "R20")
      (value "Rc13")
      (footprint "Res0402ERJ:RC0402N")
      (description "Resistor")
      (fields
        (field (name "ALTIUM_VALUE") "3.32K")
        (field (name "MANUFACTURER") "Panasonic")
        (field (name "TOLERANCE") "1%")
      )
      (libsource (lib "Miscellaneous Devices") (part "Res2"))
    )
    (comp (ref "R21")
      (value "Rf12")
      (footprint "Res0402ERJ:RC0402N")
      (description "Resistor")
      (fields
        (field (name "ALTIUM_VALUE") "35.7K")
        (field (name "MANUFACTURER") "Panasonic")
        (field (name "TOLERANCE") "1%")
      )
      (libsource (lib "") (part "Res2_3"))
    )
    (comp (ref "R22")
      (value "Rc13")
      (footprint "Res0402ERJ:RC0402N")
      (description "Resistor")
      (fields
        (field (name "ALTIUM_VALUE") "2.37K")
        (field (name "MANUFACTURER") "Panasonic")
        (field (name "TOLERANCE") "1%")
      )
      (libsource (lib "Miscellaneous Devices") (part "Res2"))
    )
    (comp (ref "R23")
      (value "Rf22")
      (footprint "Res0402ERJ:RC0402N")
      (description "Resistor")
      (fields
        (field (name "ALTIUM_VALUE") "28.7K")
        (field (name "MANUFACTURER") "Panasonic")
        (field (name "TOLERANCE") "1%")
      )
      (libsource (lib "") (part "Res2_2"))
    )
    (comp (ref "R24")
      (value "Rc14")
      (footprint "Res0402ERJ:RC0402N")
      (description "Resistor")
      (fields
        (field (name "ALTIUM_VALUE") "1.69K")
        (field (name "MANUFACTURER") "Panasonic")
        (field (name "TOLERANCE") "1%")
      )
      (libsource (lib "Miscellaneous Devices") (part "Res2"))
    )
    (comp (ref "R25")
      (value "1%")
      (footprint "Res0402ERJ:RC0402N")
      (description "Resistor")
      (fields
        (field (name "ALTIUM_VALUE") "470K")
        (field (name "MANUFACTURER") "Panasonic")
        (field (name "PARTNUMBER") "ERJ-2RKF4703X")
      )
      (libsource (lib "") (part "Res2_2"))
    )
    (comp (ref "R26")
      (value "Rt")
      (footprint "Res0402ERJ:RC0402N")
      (description "Resistor")
      (fields
        (field (name "ALTIUM_VALUE") "68.1K")
        (field (name "MANUFACTURER") "Panasonic")
        (field (name "TOLERANCE") "1%")
      )
      (libsource (lib "Miscellaneous Devices") (part "Res2"))
    )
    (comp (ref "R27")
      (value "Rf13")
      (footprint "Res0402ERJ:RC0402N")
      (description "Resistor")
      (fields
        (field (name "ALTIUM_VALUE") "41.2K")
        (field (name "MANUFACTURER") "Panasonic")
        (field (name "TOLERANCE") "1%")
      )
      (libsource (lib "") (part "Res2_3"))
    )
    (comp (ref "R28")
      (value "Rf23")
      (footprint "Res0402ERJ:RC0402N")
      (description "Resistor")
      (fields
        (field (name "ALTIUM_VALUE") "13.3K")
        (field (name "MANUFACTURER") "Panasonic")
        (field (name "TOLERANCE") "1%")
      )
      (libsource (lib "") (part "Res2_2"))
    )
    (comp (ref "R29")
      (value "680 ohms")
      (footprint "Res0402ERJ:RC0402N")
      (description "Resistor")
      (fields (field (name "MANUFACTURER") "Panasonic") (field (name "TOLERANCE") "1%"))
      (libsource (lib "") (part "Res2_3"))
    )
    (comp (ref "R30")
      (value "Rt1")
      (footprint "Res0402ERJ:RC0402N")
      (description "Resistor")
      (fields
        (field (name "ALTIUM_VALUE") "0 Ohms")
        (field (name "MANUFACTURER") "Panasonic")
        (field (name "TOLERANCE") "5%")
      )
      (libsource (lib "Miscellaneous Devices") (part "Res2"))
    )
    (comp (ref "R31")
      (value "Rf14")
      (footprint "Res0402ERJ:RC0402N")
      (description "Resistor")
      (fields
        (field (name "ALTIUM_VALUE") "19.6K")
        (field (name "MANUFACTURER") "Panasonic")
        (field (name "TOLERANCE") "1%")
      )
      (libsource (lib "") (part "Res2_3"))
    )
    (comp (ref "R32")
      (value "Rf24")
      (footprint "Res0402ERJ:RC0402N")
      (description "Resistor")
      (fields
        (field (name "ALTIUM_VALUE") "28.7K")
        (field (name "MANUFACTURER") "Panasonic")
        (field (name "TOLERANCE") "1%")
      )
      (libsource (lib "") (part "Res2_2"))
    )
    (comp (ref "R33")
      (value "Rt2")
      (footprint "Res0402ERJ:RC0402N")
      (description "Resistor")
      (fields
        (field (name "ALTIUM_VALUE") "0 Ohms")
        (field (name "MANUFACTURER") "Panasonic")
        (field (name "TOLERANCE") "5%")
      )
      (libsource (lib "Miscellaneous Devices") (part "Res2"))
    )
    (comp (ref "R34")
      (value "240K")
      (footprint "Res0402ERJ:RC0402N")
      (description "Resistor")
      (fields (field (name "MANUFACTURER") "Panasonic") (field (name "TOLERANCE") "1%"))
      (libsource (lib "") (part "Res2_2"))
    )
    (comp (ref "R35")
      (value "Rtop")
      (footprint "Res0402ERJ:RC0402N")
      (description "Resistor")
      (fields
        (field (name "ALTIUM_VALUE") "16K")
        (field (name "MANUFACTURER") "Panasonic")
        (field (name "TOLERANCE") "1%")
      )
      (libsource (lib "") (part "Res2_3"))
    )
    (comp (ref "R36")
      (value "Rbot")
      (footprint "Res0402ERJ:RC0402N")
      (description "Resistor")
      (fields
        (field (name "ALTIUM_VALUE") "10K")
        (field (name "MANUFACTURER") "Panasonic")
        (field (name "TOLERANCE") "1%")
      )
      (libsource (lib "") (part "Res2_1"))
    )
    (comp (ref "R37")
      (value "430")
      (footprint "Res0402ERJ:RC0402N")
      (description "Resistor")
      (fields (field (name "MANUFACTURER") "Panasonic") (field (name "TOLERANCE") "1%"))
      (libsource (lib "") (part "Res2_2"))
    )
    (comp (ref "R38")
      (value "1%")
      (footprint "Res0402ERJ:RC0402N")
      (description "Resistor")
      (fields
        (field (name "ALTIUM_VALUE") "10 ohms")
        (field (name "MANUFACTURER") "Panasonic")
        (field (name "PARTNUMBER") "ERJ-2RKF10R0X")
      )
      (libsource (lib "Miscellaneous Devices") (part "Res2"))
    )
    (comp (ref "R39")
      (value "30.1 K")
      (footprint "Res0402ERJ:RC0402N")
      (description "Resistor")
      (fields (field (name "MANUFACTURER") "Panasonic") (field (name "TOLERANCE") "1%"))
      (libsource (lib "") (part "Res2_2"))
    )
    (comp (ref "R40")
      (value "Rtop")
      (footprint "Res0402ERJ:RC0402N")
      (description "Resistor")
      (fields
        (field (name "ALTIUM_VALUE") "20K")
        (field (name "MANUFACTURER") "Panasonic")
        (field (name "TOLERANCE") "1%")
      )
      (libsource (lib "") (part "Res2_1"))
    )
    (comp (ref "R41")
      (value "Rbot")
      (footprint "Res0402ERJ:RC0402N")
      (description "Resistor")
      (fields
        (field (name "ALTIUM_VALUE") "10K")
        (field (name "MANUFACTURER") "Panasonic")
        (field (name "TOLERANCE") "1%")
      )
      (libsource (lib "") (part "Res2_1"))
    )
    (comp (ref "R42")
      (value "Rtop")
      (footprint "Res0402ERJ:RC0402N")
      (description "Resistor")
      (fields
        (field (name "ALTIUM_VALUE") "16K")
        (field (name "MANUFACTURER") "Panasonic")
        (field (name "TOLERANCE") "1%")
      )
      (libsource (lib "") (part "Res2_3"))
    )
    (comp (ref "R43")
      (value "Rbot")
      (footprint "Res0402ERJ:RC0402N")
      (description "Resistor")
      (fields
        (field (name "ALTIUM_VALUE") "10K")
        (field (name "MANUFACTURER") "Panasonic")
        (field (name "TOLERANCE") "1%")
      )
      (libsource (lib "") (part "Res2_1"))
    )
    (comp (ref "R114")
      (value "1%")
      (footprint "Res0402ERJ:RC0402N")
      (description "Resistor")
      (fields
        (field (name "ALTIUM_VALUE") "3K")
        (field (name "MANUFACTURER") "Panasonic")
        (field (name "PARTNUMBER") "ERJ-2RKF10R0X")
      )
      (libsource (lib "") (part "Res2_2"))
    )
    (comp (ref "R115")
      (value "1%")
      (footprint "Res0402ERJ:RC0402N")
      (description "Resistor")
      (fields
        (field (name "ALTIUM_VALUE") "2K")
        (field (name "MANUFACTURER") "Panasonic")
        (field (name "PARTNUMBER") "ERJ-2RKF10R0X")
      )
      (libsource (lib "") (part "Res2_2"))
    )
    (comp (ref "U4")
      (value "ADP5054ACPZ-R7")
      (footprint "adp5054:CP_48_13")
      (description "Quad Buck Regulator")
      (fields (field (name "MANUFACTURER") "Analog Devices"))
      (libsource (lib "adp5054") (part "ADP5054ACPZ-R7"))
    )
    (comp (ref "U5")
      (value "LTC4412")
      (footprint "LTC4412:TSOT-23_S6")
      (description "Power Path Selector")
      (fields (field (name "MANUFACTURER") "Analog Devices") (field (name "PARTNUMBER") "LTC4412ES6#TRMPBF"))
      (libsource (lib "LTC4412") (part "LTC4412ES6#PBF"))
    )
    (comp (ref "U6")
      (value "ADP1755ACPZ-R7")
      (footprint "ADP1755A:CP_16_4")
      (description "Power Regulator")
      (fields (field (name "MANUFACTURER") "Analog Devices"))
      (libsource (lib "ADP1755A") (part "ADP1755ACPZ-R7"))
    )
    (comp (ref "U7")
      (value "TPS76801QDR")
      (footprint "TPS76801QDR:D8")
      (description "Power Regulator")
      (fields (field (name "MANUFACTURER") "Texas Instruments"))
      (libsource (lib "TPS76801QDR") (part "TPS76801QDR"))
    )
    (comp (ref "U8")
      (value "ADP2164ACPZ-R7")
      (footprint "ADP2164:CP_16_26")
      (description "Power Regulator")
      (fields (field (name "MANUFACTURER") "Analog Devices"))
      (libsource (lib "ADP2164") (part "ADP2164ACPZ-R7"))
    )
    (comp (ref "U9")
      (value "ADP1755ACPZ-R7")
      (footprint "ADP1755A:CP_16_4")
      (description "Power Regulator")
      (fields (field (name "MANUFACTURER") "Analog Devices"))
      (libsource (lib "ADP1755A") (part "ADP1755ACPZ-R7"))
    )
  )
  (nets
    (net (code "1") (name "/1.3V_A_IN") (class "Default")
      (node (ref "P4") (pin "1") (pinfunction "1_1") (pintype "passive"))
    )
    (net (code "2") (name "/1.3V_A_OUT") (class "Default")
      (node (ref "C92") (pin "2") (pinfunction "2_2") (pintype "passive"))
      (node (ref "C93") (pin "2") (pinfunction "2_2") (pintype "passive"))
      (node (ref "C94") (pin "2") (pinfunction "2_2") (pintype "passive"))
      (node (ref "C95") (pin "2") (pinfunction "2_2") (pintype "passive"))
      (node (ref "C96") (pin "2") (pinfunction "2_2") (pintype "passive"))
      (node (ref "C97") (pin "2") (pinfunction "2_2") (pintype "passive"))
      (node (ref "P4") (pin "2") (pinfunction "2_2") (pintype "passive"))
      (node (ref "R35") (pin "2") (pinfunction "2_2") (pintype "passive"))
      (node (ref "U6") (pin "10") (pinfunction "VOUT_10") (pintype "passive"))
      (node (ref "U6") (pin "11") (pinfunction "VOUT_11") (pintype "passive"))
      (node (ref "U6") (pin "12") (pinfunction "VOUT_12") (pintype "passive"))
      (node (ref "U6") (pin "13") (pinfunction "VOUT_13") (pintype "passive"))
      (node (ref "U6") (pin "14") (pinfunction "VOUT_14") (pintype "passive"))
    )
    (net (code "3") (name "/1.3V_B_IN") (class "Default")
      (node (ref "P5") (pin "1") (pinfunction "1_1") (pintype "passive"))
    )
    (net (code "4") (name "/1.3V_B_OUT") (class "Default")
      (node (ref "C132") (pin "2") (pinfunction "2_2") (pintype "passive"))
      (node (ref "C133") (pin "2") (pinfunction "2_2") (pintype "passive"))
      (node (ref "C134") (pin "2") (pinfunction "2_2") (pintype "passive"))
      (node (ref "C135") (pin "2") (pinfunction "2_2") (pintype "passive"))
      (node (ref "C136") (pin "2") (pinfunction "2_2") (pintype "passive"))
      (node (ref "C137") (pin "2") (pinfunction "2_2") (pintype "passive"))
      (node (ref "P5") (pin "2") (pinfunction "2_2") (pintype "passive"))
      (node (ref "R42") (pin "2") (pinfunction "2_2") (pintype "passive"))
      (node (ref "U9") (pin "10") (pinfunction "VOUT_10") (pintype "passive"))
      (node (ref "U9") (pin "11") (pinfunction "VOUT_11") (pintype "passive"))
      (node (ref "U9") (pin "12") (pinfunction "VOUT_12") (pintype "passive"))
      (node (ref "U9") (pin "13") (pinfunction "VOUT_13") (pintype "passive"))
      (node (ref "U9") (pin "14") (pinfunction "VOUT_14") (pintype "passive"))
    )
    (net (code "5") (name "/1.8VAD9364") (class "Default")
      (node (ref "C126") (pin "2") (pinfunction "2_2") (pintype "passive"))
      (node (ref "C127") (pin "2") (pinfunction "2_2") (pintype "passive"))
      (node (ref "C128") (pin "2") (pinfunction "2_2") (pintype "passive"))
      (node (ref "C86") (pin "2") (pinfunction "2_2") (pintype "passive"))
      (node (ref "C87") (pin "2") (pinfunction "2_2") (pintype "passive"))
      (node (ref "C88") (pin "2") (pinfunction "2_2") (pintype "passive"))
      (node (ref "E2") (pin "2") (pintype "passive"))
      (node (ref "E3") (pin "1") (pintype "passive"))
      (node (ref "R40") (pin "1") (pinfunction "1_1") (pintype "passive"))
      (node (ref "U6") (pin "1") (pinfunction "VIN_1") (pintype "passive"))
      (node (ref "U6") (pin "15") (pinfunction "VIN_15") (pintype "passive"))
      (node (ref "U6") (pin "16") (pinfunction "VIN_16") (pintype "passive"))
      (node (ref "U6") (pin "2") (pinfunction "VIN_2") (pintype "passive"))
      (node (ref "U6") (pin "3") (pinfunction "VIN_3") (pintype "passive"))
      (node (ref "U6") (pin "4") (pinfunction "EN_4") (pintype "passive"))
      (node (ref "U9") (pin "1") (pinfunction "VIN_1") (pintype "passive"))
      (node (ref "U9") (pin "15") (pinfunction "VIN_15") (pintype "passive"))
      (node (ref "U9") (pin "16") (pinfunction "VIN_16") (pintype "passive"))
      (node (ref "U9") (pin "2") (pinfunction "VIN_2") (pintype "passive"))
      (node (ref "U9") (pin "3") (pinfunction "VIN_3") (pintype "passive"))
      (node (ref "U9") (pin "4") (pinfunction "EN_4") (pintype "passive"))
    )
    (net (code "6") (name "/BST1") (class "Default")
      (node (ref "C64") (pin "1") (pinfunction "1_1") (pintype "passive"))
      (node (ref "U4") (pin "32") (pinfunction "BST1_32") (pintype "passive"))
    )
    (net (code "7") (name "/BST2") (class "Default")
      (node (ref "C70") (pin "1") (pinfunction "1_1") (pintype "passive"))
      (node (ref "U4") (pin "28") (pinfunction "BST2_28") (pintype "passive"))
    )
    (net (code "8") (name "/BST3") (class "Default")
      (node (ref "C76") (pin "1") (pinfunction "1_1") (pintype "passive"))
      (node (ref "U4") (pin "1") (pinfunction "BST3_1") (pintype "passive"))
    )
    (net (code "9") (name "/BST4") (class "Default")
      (node (ref "C84") (pin "1") (pinfunction "1_1") (pintype "passive"))
      (node (ref "U4") (pin "12") (pinfunction "BST4_12") (pintype "passive"))
    )
    (net (code "10") (name "/COMP1") (class "Default")
      (node (ref "R19") (pin "2") (pinfunction "2_2") (pintype "passive"))
      (node (ref "U4") (pin "40") (pinfunction "COMP1_40") (pintype "passive"))
    )
    (net (code "11") (name "/COMP2") (class "Default")
      (node (ref "R20") (pin "2") (pinfunction "2_2") (pintype "passive"))
      (node (ref "U4") (pin "20") (pinfunction "COMP2_20") (pintype "passive"))
    )
    (net (code "12") (name "/COMP3") (class "Default")
      (node (ref "R22") (pin "2") (pinfunction "2_2") (pintype "passive"))
      (node (ref "U4") (pin "47") (pinfunction "COMP3_47") (pintype "passive"))
    )
    (net (code "13") (name "/COMP4") (class "Default")
      (node (ref "R24") (pin "2") (pinfunction "2_2") (pintype "passive"))
      (node (ref "U4") (pin "15") (pinfunction "COMP4_15") (pintype "passive"))
    )
    (net (code "14") (name "/DL1") (class "Default")
      (node (ref "Q1") (pin "2") (pinfunction "G1_2") (pintype "passive"))
      (node (ref "U4") (pin "31") (pinfunction "DL1_31") (pintype "passive"))
    )
    (net (code "15") (name "/DL2") (class "Default")
      (node (ref "Q1") (pin "4") (pinfunction "G2_4") (pintype "passive"))
      (node (ref "U4") (pin "29") (pinfunction "DL2_29") (pintype "passive"))
    )
    (net (code "16") (name "/ENABLE_1V") (class "Default")
      (node (ref "R114") (pin "1") (pinfunction "1_1") (pintype "passive"))
      (node (ref "R115") (pin "2") (pinfunction "2_2") (pintype "passive"))
      (node (ref "U4") (pin "39") (pinfunction "EN1_39") (pintype "passive"))
    )
    (net (code "17") (name "/FB1") (class "Default")
      (node (ref "C65") (pin "1") (pinfunction "1_1") (pintype "passive"))
      (node (ref "R17") (pin "1") (pinfunction "1_1") (pintype "passive"))
      (node (ref "R18") (pin "2") (pinfunction "2_2") (pintype "passive"))
      (node (ref "U4") (pin "41") (pinfunction "FB1_41") (pintype "passive"))
    )
    (net (code "18") (name "/FB2") (class "Default")
      (node (ref "C72") (pin "1") (pinfunction "1_1") (pintype "passive"))
      (node (ref "R21") (pin "1") (pinfunction "1_1") (pintype "passive"))
      (node (ref "R23") (pin "2") (pinfunction "2_2") (pintype "passive"))
      (node (ref "U4") (pin "19") (pinfunction "FB2_19") (pintype "passive"))
    )
    (net (code "19") (name "/FB3") (class "Default")
      (node (ref "C82") (pin "1") (pinfunction "1_1") (pintype "passive"))
      (node (ref "R27") (pin "1") (pinfunction "1_1") (pintype "passive"))
      (node (ref "R28") (pin "2") (pinfunction "2_2") (pintype "passive"))
      (node (ref "U4") (pin "46") (pinfunction "FB3_46") (pintype "passive"))
    )
    (net (code "20") (name "/FB4") (class "Default")
      (node (ref "C85") (pin "1") (pinfunction "1_1") (pintype "passive"))
      (node (ref "R31") (pin "1") (pinfunction "1_1") (pintype "passive"))
      (node (ref "R32") (pin "2") (pinfunction "2_2") (pintype "passive"))
      (node (ref "U4") (pin "16") (pinfunction "FB4_16") (pintype "passive"))
    )
    (net (code "21") (name "/FB_USB") (class "Default")
      (node (ref "R37") (pin "1") (pinfunction "1_1") (pintype "passive"))
      (node (ref "R39") (pin "2") (pinfunction "2_2") (pintype "passive"))
      (node (ref "U7") (pin "7") (pinfunction "FB/NC_7") (pintype "passive"))
    )
    (net (code "22") (name "/Jack_IN") (class "Default")
      (node (ref "F1") (pin "1") (pinfunction "1_1") (pintype "passive"))
      (node (ref "J5") (pin "1") (pinfunction "1_1") (pintype "power_in"))
      (node (ref "J5") (pin "1A") (pinfunction "1A_1A") (pintype "power_in"))
      (node (ref "J5") (pin "1B") (pinfunction "1B_1B") (pintype "power_in"))
    )
    (net (code "23") (name "/PWRGD") (class "Default")
      (node (ref "Q3") (pin "1") (pinfunction "G_1") (pintype "passive"))
      (node (ref "U4") (pin "17") (pinfunction "PWRGD_17") (pintype "passive"))
    )
    (net (code "24") (name "/RT") (class "Default")
      (node (ref "R26") (pin "1") (pinfunction "1_1") (pintype "passive"))
      (node (ref "U4") (pin "42") (pinfunction "RT_42") (pintype "passive"))
    )
    (net (code "25") (name "/SW1") (class "Default")
      (node (ref "C64") (pin "2") (pinfunction "2_2") (pintype "passive"))
      (node (ref "L3") (pin "1") (pinfunction "1_1") (pintype "passive"))
      (node (ref "Q1") (pin "7") (pinfunction "D1_7") (pintype "passive"))
      (node (ref "Q1") (pin "8") (pinfunction "D1_8") (pintype "passive"))
      (node (ref "U4") (pin "33") (pinfunction "SW1_33") (pintype "passive"))
      (node (ref "U4") (pin "34") (pinfunction "SW1_34") (pintype "passive"))
      (node (ref "U4") (pin "35") (pinfunction "SW1_35") (pintype "passive"))
    )
    (net (code "26") (name "/SW2") (class "Default")
      (node (ref "C70") (pin "2") (pinfunction "2_2") (pintype "passive"))
      (node (ref "L4") (pin "1") (pinfunction "1_1") (pintype "passive"))
      (node (ref "Q1") (pin "5") (pinfunction "D2_5") (pintype "passive"))
      (node (ref "Q1") (pin "6") (pinfunction "D2_6") (pintype "passive"))
      (node (ref "U4") (pin "25") (pinfunction "SW2_25") (pintype "passive"))
      (node (ref "U4") (pin "26") (pinfunction "SW2_26") (pintype "passive"))
      (node (ref "U4") (pin "27") (pinfunction "SW2_27") (pintype "passive"))
    )
    (net (code "27") (name "/SW3") (class "Default")
      (node (ref "C76") (pin "2") (pinfunction "2_2") (pintype "passive"))
      (node (ref "L5") (pin "1") (pinfunction "1_1") (pintype "passive"))
      (node (ref "U4") (pin "4") (pinfunction "SW3_4") (pintype "passive"))
      (node (ref "U4") (pin "5") (pinfunction "SW3_5") (pintype "passive"))
    )
    (net (code "28") (name "/SW4") (class "Default")
      (node (ref "C84") (pin "2") (pinfunction "2_2") (pintype "passive"))
      (node (ref "L6") (pin "1") (pinfunction "1_1") (pintype "passive"))
      (node (ref "U4") (pin "8") (pinfunction "SW4_8") (pintype "passive"))
      (node (ref "U4") (pin "9") (pinfunction "SW4_9") (pintype "passive"))
    )
    (net (code "29") (name "/SYNC{slash}MODE") (class "Default")
      (node (ref "R30") (pin "1") (pinfunction "1_1") (pintype "passive"))
      (node (ref "R33") (pin "1") (pinfunction "1_1") (pintype "passive"))
      (node (ref "U4") (pin "44") (pinfunction "SYNC/MODE_44") (pintype "passive"))
    )
    (net (code "30") (name "/VDDA_GPO") (class "Default")
      (node (ref "P7") (pin "2") (pinfunction "2_2") (pintype "passive"))
    )
    (net (code "31") (name "/VDDA_GPO_OUT") (class "Default")
      (node (ref "C103") (pin "2") (pinfunction "2_2") (pintype "passive"))
      (node (ref "E1") (pin "2") (pintype "passive"))
      (node (ref "P7") (pin "1") (pinfunction "1_1") (pintype "passive"))
    )
    (net (code "32") (name "/VDD_ADP5054") (class "Default")
      (node (ref "C66") (pin "2") (pinfunction "2_2") (pintype "passive"))
      (node (ref "U4") (pin "43") (pinfunction "VDD_43") (pintype "passive"))
    )
    (net (code "33") (name "/VDD_INTERFACE") (class "Default")
      (node (ref "P6") (pin "2") (pinfunction "2_2") (pintype "passive"))
    )
    (net (code "34") (name "/VDD_INTERFACE_OUT") (class "Default")
      (node (ref "C120") (pin "2") (pinfunction "2_2") (pintype "passive"))
      (node (ref "C121") (pin "2") (pinfunction "2_2") (pintype "passive"))
      (node (ref "E3") (pin "2") (pintype "passive"))
      (node (ref "P6") (pin "1") (pinfunction "1_1") (pintype "passive"))
    )
    (net (code "35") (name "/VIN") (class "Default")
      (node (ref "R38") (pin "2") (pinfunction "2_2") (pintype "passive"))
      (node (ref "U8") (pin "1") (pinfunction "SYNC_1") (pintype "passive"))
      (node (ref "U8") (pin "14") (pinfunction "VIN_14") (pintype "passive"))
      (node (ref "U8") (pin "15") (pinfunction "EN_15") (pintype "passive"))
      (node (ref "U8") (pin "3") (pinfunction "TRK_3") (pintype "passive"))
    )
    (net (code "36") (name "/VREG") (class "Default")
      (node (ref "C81") (pin "1") (pinfunction "1_1") (pintype "passive"))
      (node (ref "R29") (pin "2") (pinfunction "2_2") (pintype "passive"))
      (node (ref "R30") (pin "2") (pinfunction "2_2") (pintype "passive"))
      (node (ref "U4") (pin "45") (pinfunction "VREG_45") (pintype "passive"))
    )
    (net (code "37") (name "/Vextern") (class "Default")
      (node (ref "F1") (pin "2") (pinfunction "2_2") (pintype "passive"))
      (node (ref "Q2") (pin "5") (pinfunction "D_5") (pintype "passive"))
      (node (ref "Q2") (pin "6") (pinfunction "D_6") (pintype "passive"))
    )
    (net (code "38") (name "1.2V") (class "Default")
      (node (ref "C109") (pin "1") (pinfunction "1_1") (pintype "passive"))
      (node (ref "R34") (pin "1") (pinfunction "1_1") (pintype "passive"))
      (node (ref "R37") (pin "2") (pinfunction "2_2") (pintype "passive"))
      (node (ref "U7") (pin "5") (pinfunction "OUT_5") (pintype "output"))
      (node (ref "U7") (pin "6") (pinfunction "OUT_6") (pintype "output"))
    )
    (net (code "39") (name "1.8V") (class "Default")
      (node (ref "C68") (pin "2") (pinfunction "2_2") (pintype "passive"))
      (node (ref "C72") (pin "2") (pinfunction "2_2") (pintype "passive"))
      (node (ref "L4") (pin "2") (pinfunction "2_2") (pintype "passive"))
      (node (ref "R21") (pin "2") (pinfunction "2_2") (pintype "passive"))
      (node (ref "U4") (pin "48") (pinfunction "EN3_48") (pintype "passive"))
    )
    (net (code "40") (name "1.35V") (class "Default")
      (node (ref "C83") (pin "2") (pinfunction "2_2") (pintype "passive"))
      (node (ref "C85") (pin "2") (pinfunction "2_2") (pintype "passive"))
      (node (ref "L6") (pin "2") (pinfunction "2_2") (pintype "passive"))
      (node (ref "R31") (pin "2") (pinfunction "2_2") (pintype "passive"))
    )
    (net (code "41") (name "1V") (class "Default")
      (node (ref "C63") (pin "2") (pinfunction "2_2") (pintype "passive"))
      (node (ref "C65") (pin "2") (pinfunction "2_2") (pintype "passive"))
      (node (ref "L3") (pin "2") (pinfunction "2_2") (pintype "passive"))
      (node (ref "R17") (pin "2") (pinfunction "2_2") (pintype "passive"))
      (node (ref "U4") (pin "21") (pinfunction "EN2_21") (pintype "passive"))
    )
    (net (code "42") (name "3.3V") (class "Default")
      (node (ref "C108") (pin "1") (pinfunction "1_1") (pintype "passive"))
      (node (ref "C75") (pin "2") (pinfunction "2_2") (pintype "passive"))
      (node (ref "C82") (pin "2") (pinfunction "2_2") (pintype "passive"))
      (node (ref "C98") (pin "2") (pinfunction "2_2") (pintype "passive"))
      (node (ref "C99") (pin "2") (pinfunction "2_2") (pintype "passive"))
      (node (ref "L5") (pin "2") (pinfunction "2_2") (pintype "passive"))
      (node (ref "L7") (pin "1") (pinfunction "1_1") (pintype "passive"))
      (node (ref "R27") (pin "2") (pinfunction "2_2") (pintype "passive"))
      (node (ref "U4") (pin "14") (pinfunction "EN4_14") (pintype "passive"))
      (node (ref "U7") (pin "3") (pinfunction "IN_3") (pintype "input"))
      (node (ref "U7") (pin "4") (pinfunction "IN_4") (pintype "input"))
    )
    (net (code "43") (name "GND") (class "Default")
      (node (ref "C100") (pin "1") (pinfunction "1_1") (pintype "passive"))
      (node (ref "C101") (pin "1") (pinfunction "1_1") (pintype "passive"))
      (node (ref "C102") (pin "1") (pinfunction "1_1") (pintype "passive"))
      (node (ref "C103") (pin "1") (pinfunction "1_1") (pintype "passive"))
      (node (ref "C108") (pin "2") (pinfunction "2_2") (pintype "passive"))
      (node (ref "C109") (pin "2") (pinfunction "2_2") (pintype "passive"))
      (node (ref "C116") (pin "2") (pinfunction "2_2") (pintype "passive"))
      (node (ref "C117") (pin "1") (pinfunction "1_1") (pintype "passive"))
      (node (ref "C118") (pin "1") (pinfunction "1_1") (pintype "passive"))
      (node (ref "C119") (pin "1") (pinfunction "1_1") (pintype "passive"))
      (node (ref "C120") (pin "1") (pinfunction "1_1") (pintype "passive"))
      (node (ref "C121") (pin "1") (pinfunction "1_1") (pintype "passive"))
      (node (ref "C126") (pin "1") (pinfunction "1_1") (pintype "passive"))
      (node (ref "C127") (pin "1") (pinfunction "1_1") (pintype "passive"))
      (node (ref "C128") (pin "1") (pinfunction "1_1") (pintype "passive"))
      (node (ref "C129") (pin "2") (pinfunction "2_2") (pintype "passive"))
      (node (ref "C132") (pin "1") (pinfunction "1_1") (pintype "passive"))
      (node (ref "C133") (pin "1") (pinfunction "1_1") (pintype "passive"))
      (node (ref "C134") (pin "1") (pinfunction "1_1") (pintype "passive"))
      (node (ref "C135") (pin "1") (pinfunction "1_1") (pintype "passive"))
      (node (ref "C136") (pin "1") (pinfunction "1_1") (pintype "passive"))
      (node (ref "C137") (pin "1") (pinfunction "1_1") (pintype "passive"))
      (node (ref "C63") (pin "1") (pinfunction "1_1") (pintype "passive"))
      (node (ref "C66") (pin "1") (pinfunction "1_1") (pintype "passive"))
      (node (ref "C67") (pin "2") (pinfunction "2_2") (pintype "passive"))
      (node (ref "C68") (pin "1") (pinfunction "1_1") (pintype "passive"))
      (node (ref "C69") (pin "2") (pinfunction "2_2") (pintype "passive"))
      (node (ref "C71") (pin "2") (pinfunction "2_2") (pintype "passive"))
      (node (ref "C73") (pin "2") (pinfunction "2_2") (pintype "passive"))
      (node (ref "C74") (pin "1") (pinfunction "1_1") (pintype "passive"))
      (node (ref "C75") (pin "1") (pinfunction "1_1") (pintype "passive"))
      (node (ref "C77") (pin "1") (pinfunction "1_1") (pintype "passive"))
      (node (ref "C78") (pin "1") (pinfunction "1_1") (pintype "passive"))
      (node (ref "C79") (pin "1") (pinfunction "1_1") (pintype "passive"))
      (node (ref "C80") (pin "1") (pinfunction "1_1") (pintype "passive"))
      (node (ref "C81") (pin "2") (pinfunction "2_2") (pintype "passive"))
      (node (ref "C83") (pin "1") (pinfunction "1_1") (pintype "passive"))
      (node (ref "C86") (pin "1") (pinfunction "1_1") (pintype "passive"))
      (node (ref "C87") (pin "1") (pinfunction "1_1") (pintype "passive"))
      (node (ref "C88") (pin "1") (pinfunction "1_1") (pintype "passive"))
      (node (ref "C89") (pin "2") (pinfunction "2_2") (pintype "passive"))
      (node (ref "C92") (pin "1") (pinfunction "1_1") (pintype "passive"))
      (node (ref "C93") (pin "1") (pinfunction "1_1") (pintype "passive"))
      (node (ref "C94") (pin "1") (pinfunction "1_1") (pintype "passive"))
      (node (ref "C95") (pin "1") (pinfunction "1_1") (pintype "passive"))
      (node (ref "C96") (pin "1") (pinfunction "1_1") (pintype "passive"))
      (node (ref "C97") (pin "1") (pinfunction "1_1") (pintype "passive"))
      (node (ref "C98") (pin "1") (pinfunction "1_1") (pintype "passive"))
      (node (ref "C99") (pin "1") (pinfunction "1_1") (pintype "passive"))
      (node (ref "J5") (pin "2") (pinfunction "2_2") (pintype "power_in"))
      (node (ref "J5") (pin "2A") (pinfunction "2A_2A") (pintype "power_in"))
      (node (ref "J5") (pin "2B") (pinfunction "2B_2B") (pintype "power_in"))
      (node (ref "J5") (pin "3") (pinfunction "3_3") (pintype "power_in"))
      (node (ref "J5") (pin "3A") (pinfunction "3A_3A") (pintype "power_in"))
      (node (ref "J5") (pin "3B") (pinfunction "3B_3B") (pintype "power_in"))
      (node (ref "Q1") (pin "1") (pinfunction "S1_1") (pintype "passive"))
      (node (ref "Q1") (pin "3") (pinfunction "S2_3") (pintype "passive"))
      (node (ref "Q3") (pin "3") (pinfunction "S_3") (pintype "passive"))
      (node (ref "R115") (pin "1") (pinfunction "1_1") (pintype "passive"))
      (node (ref "R18") (pin "1") (pinfunction "1_1") (pintype "passive"))
      (node (ref "R23") (pin "1") (pinfunction "1_1") (pintype "passive"))
      (node (ref "R26") (pin "2") (pinfunction "2_2") (pintype "passive"))
      (node (ref "R28") (pin "1") (pinfunction "1_1") (pintype "passive"))
      (node (ref "R32") (pin "1") (pinfunction "1_1") (pintype "passive"))
      (node (ref "R33") (pin "2") (pinfunction "2_2") (pintype "passive"))
      (node (ref "R36") (pin "2") (pinfunction "2_2") (pintype "passive"))
      (node (ref "R39") (pin "1") (pinfunction "1_1") (pintype "passive"))
      (node (ref "R41") (pin "2") (pinfunction "2_2") (pintype "passive"))
      (node (ref "R43") (pin "2") (pinfunction "2_2") (pintype "passive"))
      (node (ref "U4") (pin "10") (pinfunction "PGND4_10") (pintype "passive"))
      (node (ref "U4") (pin "11") (pinfunction "PGND4_11") (pintype "passive"))
      (node (ref "U4") (pin "13") (pinfunction "CFG34_13") (pintype "passive"))
      (node (ref "U4") (pin "18") (pinfunction "CFG12_18") (pintype "passive"))
      (node (ref "U4") (pin "2") (pinfunction "PGND3_2") (pintype "passive"))
      (node (ref "U4") (pin "3") (pinfunction "PGND3_3") (pintype "passive"))
      (node (ref "U4") (pin "30") (pinfunction "PGND_30") (pintype "passive"))
      (node (ref "U4") (pin "49") (pinfunction "EP_49") (pintype "passive"))
      (node (ref "U5") (pin "2") (pinfunction "GND_2") (pintype "power_in"))
      (node (ref "U5") (pin "3") (pinfunction "CTL_3") (pintype "input"))
      (node (ref "U6") (pin "17") (pinfunction "EP_17") (pintype "passive"))
      (node (ref "U6") (pin "6") (pinfunction "GND_6") (pintype "passive"))
      (node (ref "U7") (pin "1") (pinfunction "GND_1") (pintype "power_in"))
      (node (ref "U7") (pin "2") (pinfunction "*EN_2") (pintype "input"))
      (node (ref "U8") (pin "17") (pinfunction "EP_17") (pintype "passive"))
      (node (ref "U8") (pin "2") (pinfunction "RT_2") (pintype "passive"))
      (node (ref "U8") (pin "5") (pinfunction "GND_5") (pintype "passive"))
      (node (ref "U8") (pin "6") (pinfunction "PGND_6") (pintype "passive"))
      (node (ref "U8") (pin "7") (pinfunction "PGND_7") (pintype "passive"))
      (node (ref "U8") (pin "8") (pinfunction "PGND_8") (pintype "passive"))
      (node (ref "U9") (pin "17") (pinfunction "EP_17") (pintype "passive"))
      (node (ref "U9") (pin "6") (pinfunction "GND_6") (pintype "passive"))
    )
    (net (code "44") (name "Net-(C67-Pad1)") (class "Default")
      (node (ref "C67") (pin "1") (pinfunction "1_1") (pintype "passive"))
      (node (ref "R19") (pin "1") (pinfunction "1_1") (pintype "passive"))
    )
    (net (code "45") (name "Net-(C69-Pad1)") (class "Default")
      (node (ref "C69") (pin "1") (pinfunction "1_1") (pintype "passive"))
      (node (ref "R20") (pin "1") (pinfunction "1_1") (pintype "passive"))
    )
    (net (code "46") (name "Net-(C71-Pad1)") (class "Default")
      (node (ref "C71") (pin "1") (pinfunction "1_1") (pintype "passive"))
      (node (ref "R22") (pin "1") (pinfunction "1_1") (pintype "passive"))
    )
    (net (code "47") (name "Net-(C73-Pad1)") (class "Default")
      (node (ref "C73") (pin "1") (pinfunction "1_1") (pintype "passive"))
      (node (ref "R24") (pin "1") (pinfunction "1_1") (pintype "passive"))
    )
    (net (code "48") (name "Net-(C100-Pad2)") (class "Default")
      (node (ref "C100") (pin "2") (pinfunction "2_2") (pintype "passive"))
      (node (ref "C101") (pin "2") (pinfunction "2_2") (pintype "passive"))
      (node (ref "C102") (pin "2") (pinfunction "2_2") (pintype "passive"))
      (node (ref "C116") (pin "1") (pinfunction "1_1") (pintype "passive"))
      (node (ref "E1") (pin "1") (pintype "passive"))
      (node (ref "L7") (pin "2") (pinfunction "2_2") (pintype "passive"))
      (node (ref "R38") (pin "1") (pinfunction "1_1") (pintype "passive"))
      (node (ref "U8") (pin "12") (pinfunction "PVIN_12") (pintype "passive"))
      (node (ref "U8") (pin "13") (pinfunction "PVIN_13") (pintype "passive"))
    )
    (net (code "49") (name "Net-(C117-Pad2)") (class "Default")
      (node (ref "C117") (pin "2") (pinfunction "2_2") (pintype "passive"))
      (node (ref "C118") (pin "2") (pinfunction "2_2") (pintype "passive"))
      (node (ref "C119") (pin "2") (pinfunction "2_2") (pintype "passive"))
      (node (ref "E2") (pin "1") (pintype "passive"))
      (node (ref "L8") (pin "2") (pinfunction "2_2") (pintype "passive"))
    )
    (net (code "50") (name "Net-(D3-A)") (class "Default")
      (node (ref "D3") (pin "1") (pinfunction "A_1") (pintype "passive"))
      (node (ref "R29") (pin "1") (pinfunction "1_1") (pintype "passive"))
    )
    (net (code "51") (name "Net-(D3-K)") (class "Default")
      (node (ref "D3") (pin "2") (pinfunction "K_2") (pintype "passive"))
      (node (ref "Q3") (pin "2") (pinfunction "D_2") (pintype "passive"))
    )
    (net (code "52") (name "Net-(L8-Pad1)") (class "Default")
      (node (ref "L8") (pin "1") (pinfunction "1_1") (pintype "passive"))
      (node (ref "U8") (pin "10") (pinfunction "SW_10") (pintype "passive"))
      (node (ref "U8") (pin "11") (pinfunction "SW_11") (pintype "passive"))
      (node (ref "U8") (pin "9") (pinfunction "SW_9") (pintype "passive"))
    )
    (net (code "53") (name "Net-(Q2A-G)") (class "Default")
      (node (ref "Q2") (pin "2") (pinfunction "G_2") (pintype "passive"))
      (node (ref "U5") (pin "5") (pinfunction "GATE_5") (pintype "passive"))
    )
    (net (code "54") (name "Net-(Q2B-G)") (class "Default")
      (node (ref "Q2") (pin "4") (pinfunction "G_4") (pintype "passive"))
      (node (ref "R25") (pin "1") (pinfunction "1_1") (pintype "passive"))
      (node (ref "U5") (pin "4") (pinfunction "STAT_4") (pintype "output"))
    )
    (net (code "55") (name "Net-(U6-ADJ)") (class "Default")
      (node (ref "R35") (pin "1") (pinfunction "1_1") (pintype "passive"))
      (node (ref "R36") (pin "1") (pinfunction "1_1") (pintype "passive"))
      (node (ref "U6") (pin "9") (pinfunction "ADJ_9") (pintype "passive"))
    )
    (net (code "56") (name "Net-(U6-SS)") (class "Default")
      (node (ref "C89") (pin "1") (pinfunction "1_1") (pintype "passive"))
      (node (ref "U6") (pin "7") (pinfunction "SS_7") (pintype "passive"))
    )
    (net (code "57") (name "Net-(U7-PG)") (class "Default")
      (node (ref "R34") (pin "2") (pinfunction "2_2") (pintype "passive"))
      (node (ref "U7") (pin "8") (pinfunction "PG_8") (pintype "output"))
    )
    (net (code "58") (name "Net-(U8-FB)") (class "Default")
      (node (ref "R40") (pin "2") (pinfunction "2_2") (pintype "passive"))
      (node (ref "R41") (pin "1") (pinfunction "1_1") (pintype "passive"))
      (node (ref "U8") (pin "4") (pinfunction "FB_4") (pintype "passive"))
    )
    (net (code "59") (name "Net-(U9-ADJ)") (class "Default")
      (node (ref "R42") (pin "1") (pinfunction "1_1") (pintype "passive"))
      (node (ref "R43") (pin "1") (pinfunction "1_1") (pintype "passive"))
      (node (ref "U9") (pin "9") (pinfunction "ADJ_9") (pintype "passive"))
    )
    (net (code "60") (name "Net-(U9-SS)") (class "Default")
      (node (ref "C129") (pin "1") (pinfunction "1_1") (pintype "passive"))
      (node (ref "U9") (pin "7") (pinfunction "SS_7") (pintype "passive"))
    )
    (net (code "61") (name "VBUS") (class "Default")
      (node (ref "Q2") (pin "7") (pinfunction "D_7") (pintype "passive"))
      (node (ref "Q2") (pin "8") (pinfunction "D_8") (pintype "passive"))
      (node (ref "U5") (pin "1") (pinfunction "VIN_1") (pintype "input"))
    )
    (net (code "62") (name "VSYS") (class "Default")
      (node (ref "C74") (pin "2") (pinfunction "2_2") (pintype "passive"))
      (node (ref "C77") (pin "2") (pinfunction "2_2") (pintype "passive"))
      (node (ref "C78") (pin "2") (pinfunction "2_2") (pintype "passive"))
      (node (ref "C79") (pin "2") (pinfunction "2_2") (pintype "passive"))
      (node (ref "C80") (pin "2") (pinfunction "2_2") (pintype "passive"))
      (node (ref "Q2") (pin "1") (pinfunction "S_1") (pintype "passive"))
      (node (ref "Q2") (pin "3") (pinfunction "S_3") (pintype "passive"))
      (node (ref "R114") (pin "2") (pinfunction "2_2") (pintype "passive"))
      (node (ref "R25") (pin "2") (pinfunction "2_2") (pintype "passive"))
      (node (ref "U4") (pin "22") (pinfunction "PVIN2_22") (pintype "passive"))
      (node (ref "U4") (pin "23") (pinfunction "PVIN2_23") (pintype "passive"))
      (node (ref "U4") (pin "24") (pinfunction "PVIN2_24") (pintype "passive"))
      (node (ref "U4") (pin "36") (pinfunction "PVIN1_36") (pintype "passive"))
      (node (ref "U4") (pin "37") (pinfunction "PVIN1_37") (pintype "passive"))
      (node (ref "U4") (pin "38") (pinfunction "PVIN1_38") (pintype "passive"))
      (node (ref "U4") (pin "6") (pinfunction "PVIN3_6") (pintype "passive"))
      (node (ref "U4") (pin "7") (pinfunction "PVIN4_7") (pintype "passive"))
      (node (ref "U5") (pin "6") (pinfunction "SENSE_6") (pintype "input"))
    )
    (net (code "63") (name "unconnected-(U6-NC-Pad8)") (class "Default")
      (node (ref "U6") (pin "8") (pinfunction "NC_8") (pintype "passive+no_connect"))
    )
    (net (code "64") (name "unconnected-(U6-PG-Pad5)") (class "Default")
      (node (ref "U6") (pin "5") (pinfunction "PG_5") (pintype "passive+no_connect"))
    )
    (net (code "65") (name "unconnected-(U8-PGOOD-Pad16)") (class "Default")
      (node (ref "U8") (pin "16") (pinfunction "PGOOD_16") (pintype "passive+no_connect"))
    )
    (net (code "66") (name "unconnected-(U9-NC-Pad8)") (class "Default")
      (node (ref "U9") (pin "8") (pinfunction "NC_8") (pintype "passive+no_connect"))
    )
    (net (code "67") (name "unconnected-(U9-PG-Pad5)") (class "Default")
      (node (ref "U9") (pin "5") (pinfunction "PG_5") (pintype "passive+no_connect"))
    )
  )
)
